# CD.net
KiCad netlist of a schematic drawn in EAGLE
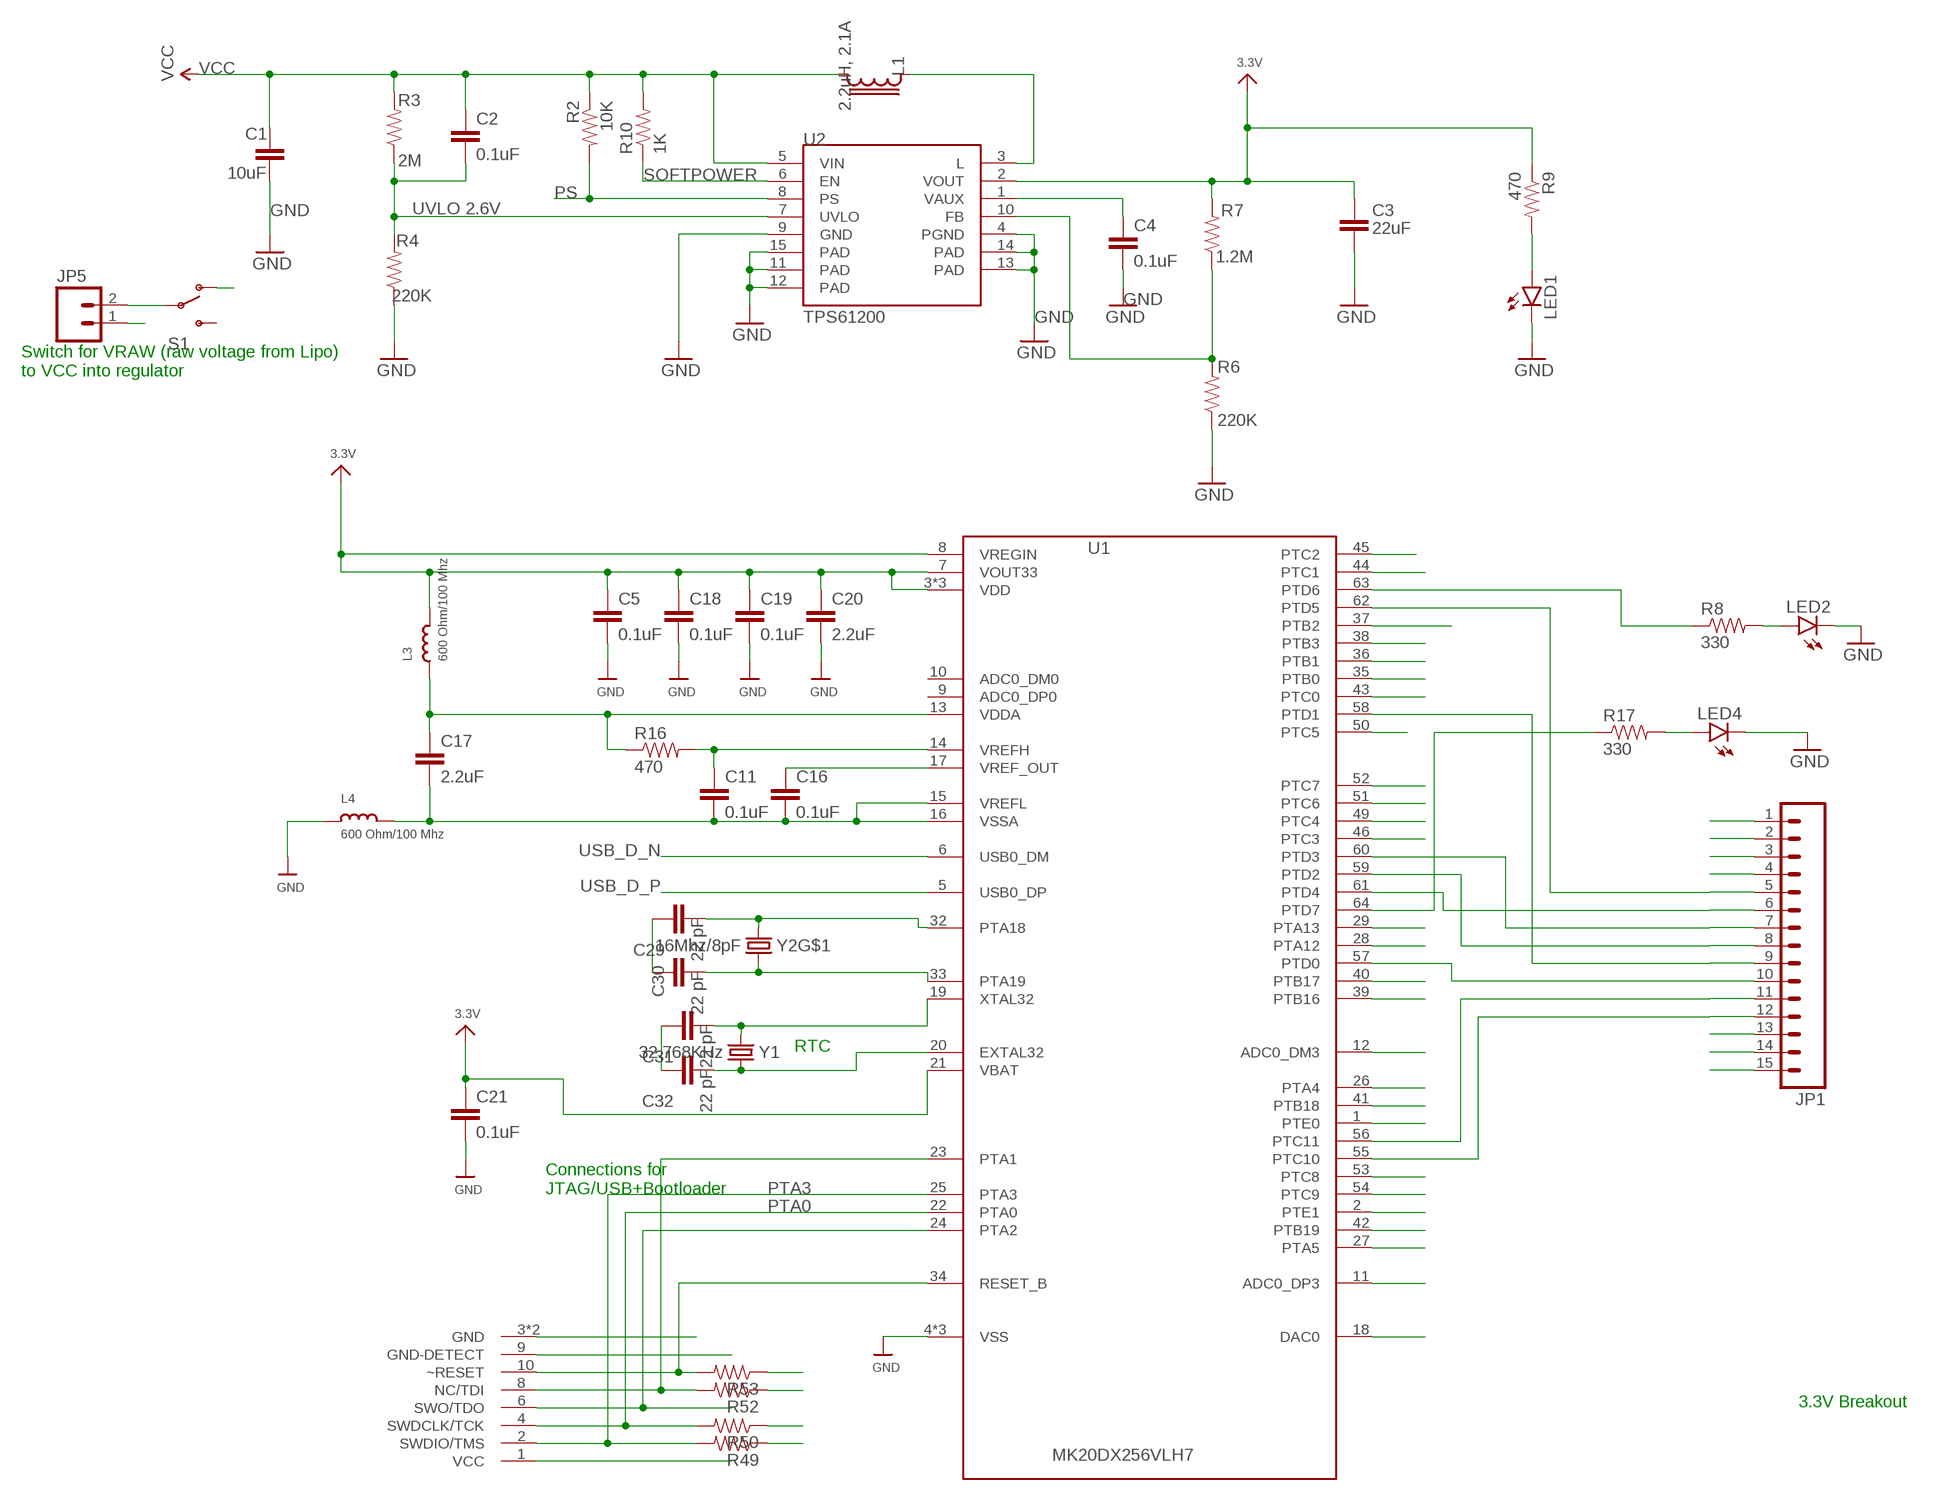
[diagram p0: schematic, sheet 1]
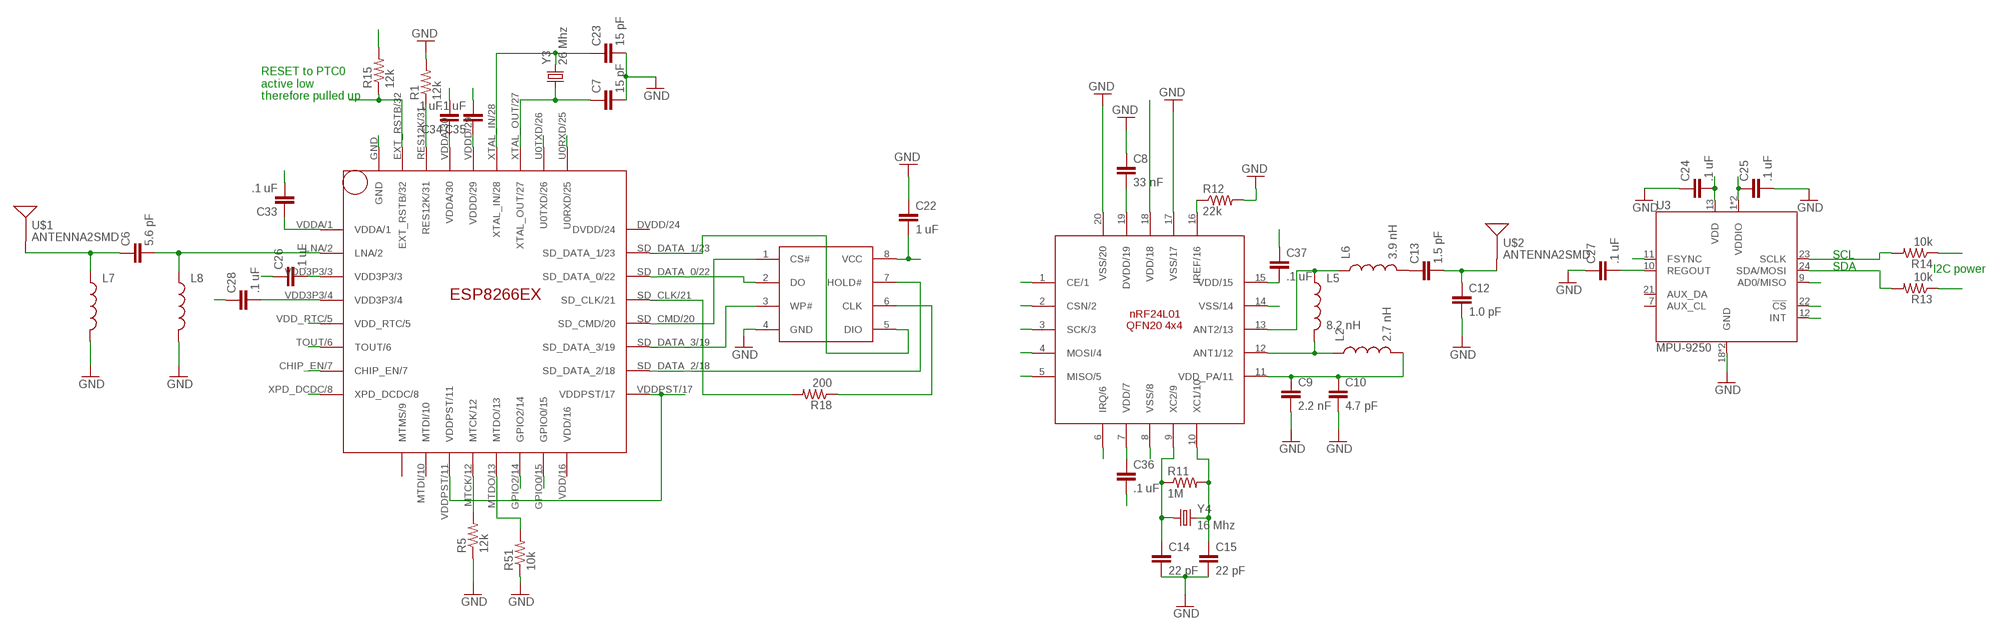
[diagram p1: schematic, sheet 2]
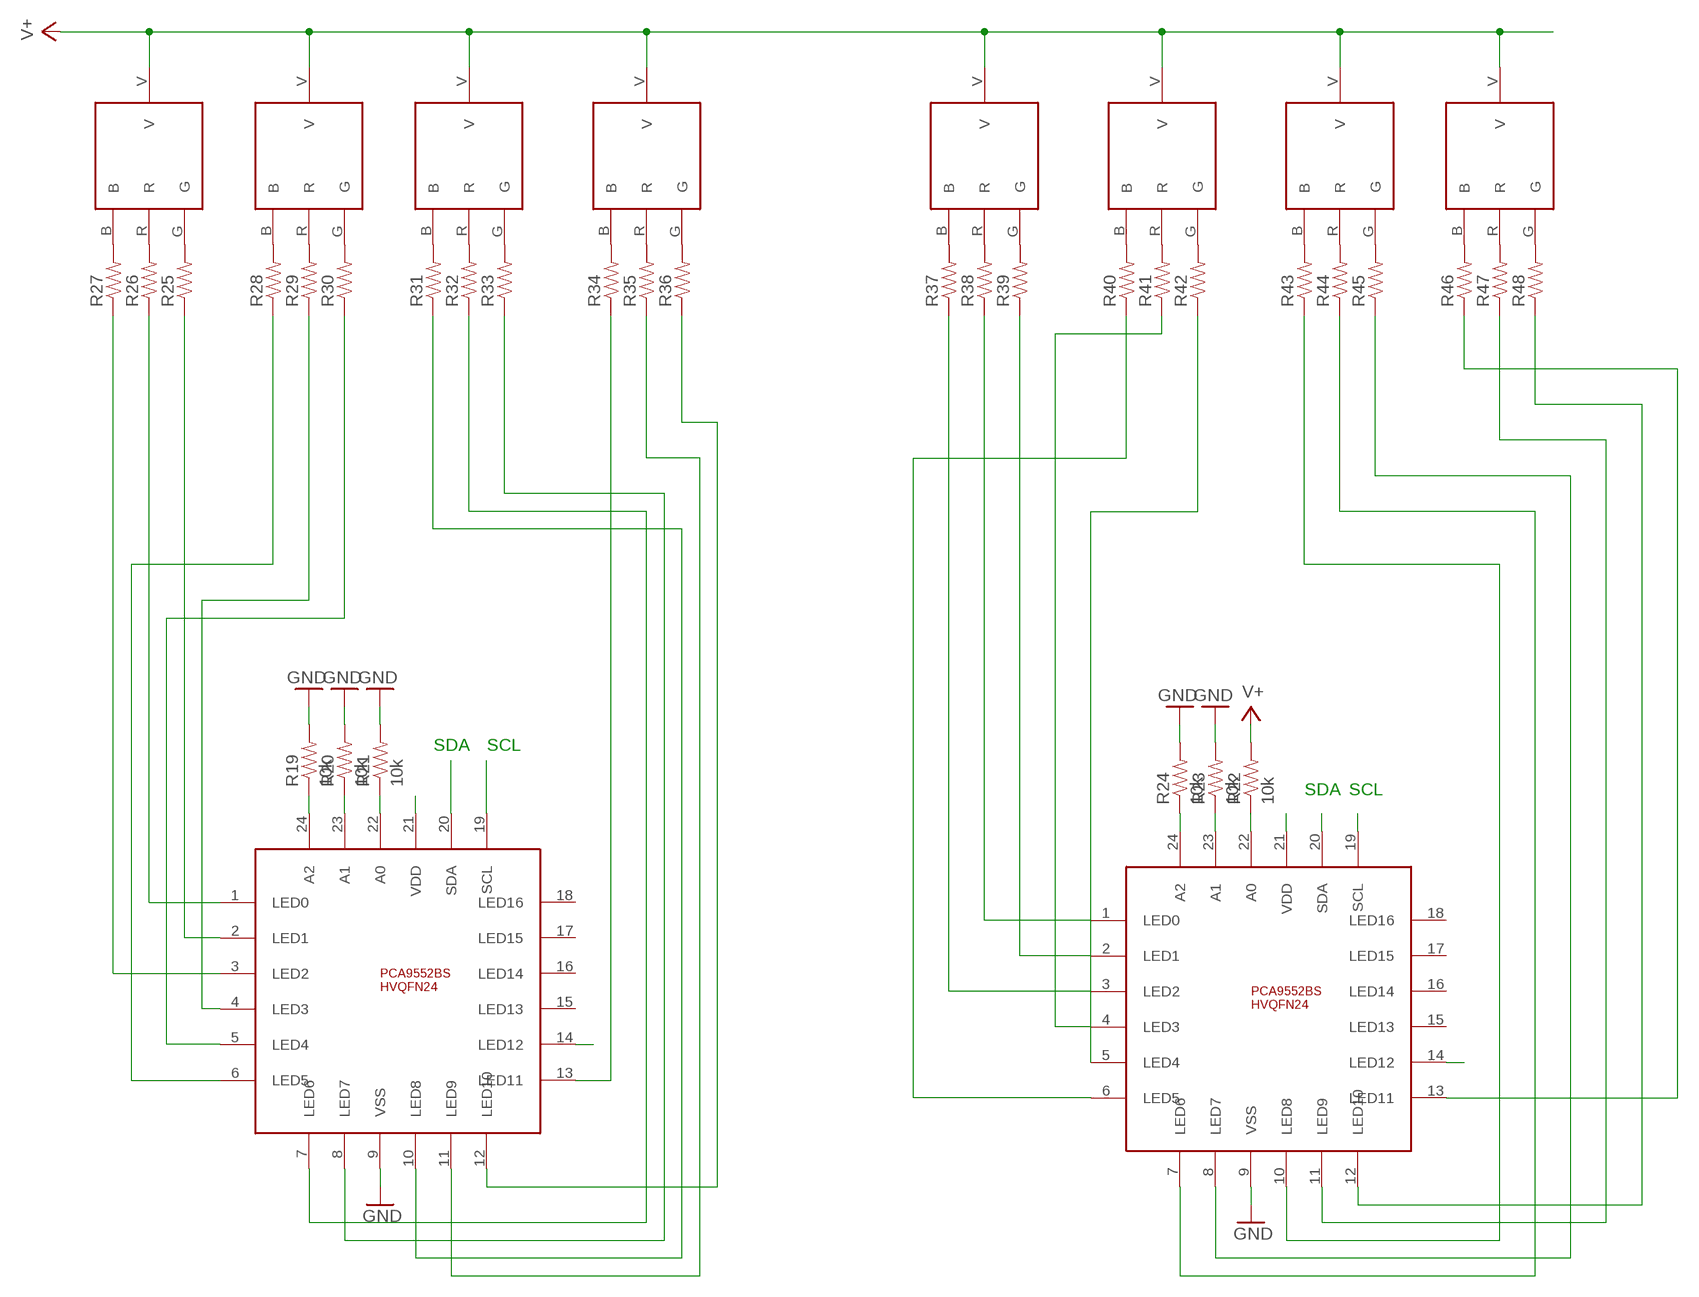
[diagram p2: schematic, sheet 3]

(export (version "E")
  (design (tool "Eeschema 10.0.6"))
  (components
    (comp (ref "C6")
      (value "5.6 pF")
      (footprint "eagle-import:0603-CAP")
      (libsource (lib "eagle-import") (part "CAP0603-CAP"))
    )
    (comp (ref "C7")
      (value "15 pF")
      (footprint "eagle-import:0603-CAP")
      (libsource (lib "eagle-import") (part "CAP0603-CAP"))
    )
    (comp (ref "C8")
      (value "33 nF")
      (footprint "eagle-import:0603-CAP")
      (libsource (lib "eagle-import") (part "CAP0603-CAP"))
    )
    (comp (ref "C9")
      (value "2.2 nF")
      (footprint "eagle-import:0603-CAP")
      (libsource (lib "eagle-import") (part "CAP0603-CAP"))
    )
    (comp (ref "C10")
      (value "4.7 pF")
      (footprint "eagle-import:0603-CAP")
      (libsource (lib "eagle-import") (part "CAP0603-CAP"))
    )
    (comp (ref "C12")
      (value "1.0 pF")
      (footprint "eagle-import:0603-CAP")
      (libsource (lib "eagle-import") (part "CAP0603-CAP"))
    )
    (comp (ref "C13")
      (value "1.5 pF")
      (footprint "eagle-import:0603-CAP")
      (libsource (lib "eagle-import") (part "CAP0603-CAP"))
    )
    (comp (ref "C14")
      (value "22 pF")
      (footprint "eagle-import:0603-CAP")
      (libsource (lib "eagle-import") (part "CAP0603-CAP"))
    )
    (comp (ref "C15")
      (value "22 pF")
      (footprint "eagle-import:0603-CAP")
      (libsource (lib "eagle-import") (part "CAP0603-CAP"))
    )
    (comp (ref "C22")
      (value "1 uF")
      (footprint "eagle-import:0603-CAP")
      (libsource (lib "eagle-import") (part "CAP0603-CAP"))
    )
    (comp (ref "C23")
      (value "15 pF")
      (footprint "eagle-import:0603-CAP")
      (libsource (lib "eagle-import") (part "CAP0603-CAP"))
    )
    (comp (ref "C24")
      (value ".1 uF")
      (footprint "eagle-import:0603-CAP")
      (libsource (lib "eagle-import") (part "CAP0603-CAP"))
    )
    (comp (ref "C25")
      (value ".1 uF")
      (footprint "eagle-import:0603-CAP")
      (libsource (lib "eagle-import") (part "CAP0603-CAP"))
    )
    (comp (ref "C26")
      (value ".1 uF")
      (footprint "eagle-import:0603-CAP")
      (libsource (lib "eagle-import") (part "CAP0603-CAP"))
    )
    (comp (ref "C27")
      (value ".1 uF")
      (footprint "eagle-import:0603-CAP")
      (libsource (lib "eagle-import") (part "CAP0603-CAP"))
    )
    (comp (ref "C28")
      (value ".1 uF")
      (footprint "eagle-import:0603-CAP")
      (libsource (lib "eagle-import") (part "CAP0603-CAP"))
    )
    (comp (ref "C33")
      (value ".1 uF")
      (footprint "eagle-import:0603-CAP")
      (libsource (lib "eagle-import") (part "CAP0603-CAP"))
    )
    (comp (ref "C34")
      (value ".1 uF")
      (footprint "eagle-import:0603-CAP")
      (libsource (lib "eagle-import") (part "CAP0603-CAP"))
    )
    (comp (ref "C35")
      (value ".1 uF")
      (footprint "eagle-import:0603-CAP")
      (libsource (lib "eagle-import") (part "CAP0603-CAP"))
    )
    (comp (ref "C36")
      (value ".1 uF")
      (footprint "eagle-import:0603-CAP")
      (libsource (lib "eagle-import") (part "CAP0603-CAP"))
    )
    (comp (ref "C37")
      (value ".1 uF")
      (footprint "eagle-import:0603-CAP")
      (libsource (lib "eagle-import") (part "CAP0603-CAP"))
    )
    (comp (ref "L2")
      (value "2.7 nH")
      (footprint "eagle-import:C0402")
      (libsource (lib "eagle-import") (part "INDUCTOR0402"))
    )
    (comp (ref "L5")
      (value "8.2 nH")
      (footprint "eagle-import:C0402")
      (libsource (lib "eagle-import") (part "INDUCTOR0402"))
    )
    (comp (ref "L6")
      (value "3.9 nH")
      (footprint "eagle-import:C0402")
      (libsource (lib "eagle-import") (part "INDUCTOR0402"))
    )
    (comp (ref "L7")
      (value "INDUCTOR30OHM,1.8A")
      (footprint "eagle-import:0603")
      (libsource (lib "eagle-import") (part "INDUCTOR30OHM,1.8A"))
    )
    (comp (ref "L8")
      (value "INDUCTOR30OHM,1.8A")
      (footprint "eagle-import:0603")
      (libsource (lib "eagle-import") (part "INDUCTOR30OHM,1.8A"))
    )
    (comp (ref "R1")
      (value "12k")
      (footprint "eagle-import:0603-RES")
      (libsource (lib "eagle-import") (part "SparkFun-Resistors_RESISTOR0603-RES"))
    )
    (comp (ref "R5")
      (value "12k")
      (footprint "eagle-import:0603-RES")
      (libsource (lib "eagle-import") (part "SparkFun-Resistors_RESISTOR0603-RES"))
    )
    (comp (ref "R11")
      (value "1M")
      (footprint "eagle-import:0603-RES")
      (libsource (lib "eagle-import") (part "SparkFun-Resistors_RESISTOR0603-RES"))
    )
    (comp (ref "R12")
      (value "22k")
      (footprint "eagle-import:0603-RES")
      (libsource (lib "eagle-import") (part "SparkFun-Resistors_RESISTOR0603-RES"))
    )
    (comp (ref "R13")
      (value "10k")
      (footprint "eagle-import:0603-RES")
      (libsource (lib "eagle-import") (part "SparkFun-Resistors_RESISTOR0603-RES"))
    )
    (comp (ref "R14")
      (value "10k")
      (footprint "eagle-import:0603-RES")
      (libsource (lib "eagle-import") (part "SparkFun-Resistors_RESISTOR0603-RES"))
    )
    (comp (ref "R15")
      (value "12k")
      (footprint "eagle-import:0603-RES")
      (libsource (lib "eagle-import") (part "SparkFun-Resistors_RESISTOR0603-RES"))
    )
    (comp (ref "R18")
      (value "200")
      (footprint "eagle-import:0603-RES")
      (libsource (lib "eagle-import") (part "SparkFun-Resistors_RESISTOR0603-RES"))
    )
    (comp (ref "R51")
      (value "10k")
      (footprint "eagle-import:0603-RES")
      (libsource (lib "eagle-import") (part "SparkFun-Resistors_RESISTOR0603-RES"))
    )
    (comp (ref "U$1")
      (value "ANTENNA2SMD")
      (footprint "eagle-import:ANTENNA-CHIP2")
      (libsource (lib "eagle-import") (part "ANTENNA2SMD"))
    )
    (comp (ref "U$2")
      (value "ANTENNA2SMD")
      (footprint "eagle-import:ANTENNA-CHIP2")
      (libsource (lib "eagle-import") (part "ANTENNA2SMD"))
    )
    (comp (ref "U$3")
      (value "25Q40")
      (footprint "eagle-import:SOP8")
      (libsource (lib "eagle-import") (part "25Q40"))
    )
    (comp (ref "U$4")
      (value "NRF24L01")
      (footprint "eagle-import:QFN20(4X4)")
      (libsource (lib "eagle-import") (part "NRF24L01"))
    )
    (comp (ref "U$6")
      (value "ESP8266EX")
      (footprint "eagle-import:QFN32")
      (libsource (lib "eagle-import") (part "ESP8266EX"))
    )
    (comp (ref "U3")
      (value "MPU-9250")
      (footprint "eagle-import:QFN-24_3MM")
      (libsource (lib "eagle-import") (part "MPU-9250"))
    )
    (comp (ref "Y3")
      (value "26 Mhz")
      (footprint "eagle-import:CRYSTAL-SMD-5X3")
      (libsource (lib "eagle-import") (part "CRYSTAL5X3"))
    )
    (comp (ref "Y4")
      (value "16 Mhz")
      (footprint "eagle-import:CRYSTAL-SMD-5X3")
      (libsource (lib "eagle-import") (part "CRYSTAL5X3"))
    )
    (comp (ref "C1")
      (value "10uF")
      (footprint "eagle-import:0603-CAP")
      (fields (field (name "MF") "Murata") (field (name "MPN") "GRM188R60J106ME47D"))
      (libsource (lib "eagle-import") (part "CAPACITOR-10UF"))
    )
    (comp (ref "C2")
      (value "0.1uF")
      (footprint "eagle-import:0603-CAP")
      (fields (field (name "MF") "Kemet") (field (name "MPN") "C0603C104J3RACTU"))
      (libsource (lib "eagle-import") (part "CAPACITOR-0.1UF"))
    )
    (comp (ref "C3")
      (value "22uF")
      (footprint "eagle-import:0603-CAP")
      (fields (field (name "MF") "Murata") (field (name "MPN") "GRM188R60J226MEA0D"))
      (libsource (lib "eagle-import") (part "CAPACITOR-22UF"))
    )
    (comp (ref "C4")
      (value "0.1uF")
      (footprint "eagle-import:0603-CAP")
      (fields (field (name "MF") "Kemet") (field (name "MPN") "C0603C104J3RACTU"))
      (libsource (lib "eagle-import") (part "CAPACITOR-0.1UF"))
    )
    (comp (ref "C5")
      (value "0.1uF")
      (footprint "eagle-import:0603-CAP")
      (fields (field (name "MF") "Kemet") (field (name "MPN") "C0603C104J3RACTU"))
      (libsource (lib "eagle-import") (part "CAPACITOR-0.1UF"))
    )
    (comp (ref "C11")
      (value "0.1uF")
      (footprint "eagle-import:0603-CAP")
      (fields (field (name "MF") "Kemet") (field (name "MPN") "C0603C104J3RACTU"))
      (libsource (lib "eagle-import") (part "CAPACITOR-0.1UF"))
    )
    (comp (ref "C16")
      (value "0.1uF")
      (footprint "eagle-import:0603-CAP")
      (fields (field (name "MF") "Kemet") (field (name "MPN") "C0603C104J3RACTU"))
      (libsource (lib "eagle-import") (part "CAPACITOR-0.1UF"))
    )
    (comp (ref "C17")
      (value "2.2uF")
      (footprint "eagle-import:0603-CAP")
      (fields (field (name "MF") "Kemet") (field (name "MPN") "C0603C225K4PACTU"))
      (libsource (lib "eagle-import") (part "CAPACITOR-2.2UF"))
    )
    (comp (ref "C18")
      (value "0.1uF")
      (footprint "eagle-import:0603-CAP")
      (fields (field (name "MF") "Kemet") (field (name "MPN") "C0603C104J3RACTU"))
      (libsource (lib "eagle-import") (part "CAPACITOR-0.1UF"))
    )
    (comp (ref "C19")
      (value "0.1uF")
      (footprint "eagle-import:0603-CAP")
      (fields (field (name "MF") "Kemet") (field (name "MPN") "C0603C104J3RACTU"))
      (libsource (lib "eagle-import") (part "CAPACITOR-0.1UF"))
    )
    (comp (ref "C20")
      (value "2.2uF")
      (footprint "eagle-import:0603-CAP")
      (fields (field (name "MF") "Kemet") (field (name "MPN") "C0603C225K4PACTU"))
      (libsource (lib "eagle-import") (part "CAPACITOR-2.2UF"))
    )
    (comp (ref "C21")
      (value "0.1uF")
      (footprint "eagle-import:0603-CAP")
      (fields (field (name "MF") "Kemet") (field (name "MPN") "C0603C104J3RACTU"))
      (libsource (lib "eagle-import") (part "CAPACITOR-0.1UF"))
    )
    (comp (ref "C29")
      (value "22 pF")
      (footprint "eagle-import:0603-CAP")
      (fields (field (name "MF") "Murata") (field (name "MPN") "GRM188R60J106ME47D"))
      (libsource (lib "eagle-import") (part "CAPACITOR-10UF"))
    )
    (comp (ref "C30")
      (value "22 pF")
      (footprint "eagle-import:0603-CAP")
      (fields (field (name "MF") "Murata") (field (name "MPN") "GRM188R60J106ME47D"))
      (libsource (lib "eagle-import") (part "CAPACITOR-10UF"))
    )
    (comp (ref "C31")
      (value "22 pF")
      (footprint "eagle-import:0603-CAP")
      (fields (field (name "MF") "Murata") (field (name "MPN") "GRM188R60J106ME47D"))
      (libsource (lib "eagle-import") (part "CAPACITOR-10UF"))
    )
    (comp (ref "C32")
      (value "22 pF")
      (footprint "eagle-import:0603-CAP")
      (fields (field (name "MF") "Murata") (field (name "MPN") "GRM188R60J106ME47D"))
      (libsource (lib "eagle-import") (part "CAPACITOR-10UF"))
    )
    (comp (ref "JP1")
      (value "M15")
      (footprint "eagle-import:1X15")
      (libsource (lib "eagle-import") (part "M15"))
    )
    (comp (ref "JP5")
      (value "M02PTH")
      (footprint "eagle-import:1X02")
      (libsource (lib "eagle-import") (part "M02PTH"))
    )
    (comp (ref "L1")
      (value "2.2uH, 2.1A")
      (footprint "eagle-import:LPS3015")
      (fields (field (name "MF") "Coilcraft") (field (name "MPN") "LPS3015-222MRB"))
      (libsource (lib "eagle-import") (part "LPS30152.2UH"))
    )
    (comp (ref "L3")
      (value "600 Ohm/100 Mhz")
      (footprint "eagle-import:0805")
      (fields (field (name "MF") "Taiyo Yuden") (field (name "MPN") "BK2125HM601-T"))
      (libsource (lib "eagle-import") (part "INDUCTOR-BK2125HM601-T"))
    )
    (comp (ref "L4")
      (value "600 Ohm/100 Mhz")
      (footprint "eagle-import:0805")
      (fields (field (name "MF") "Taiyo Yuden") (field (name "MPN") "BK2125HM601-T"))
      (libsource (lib "eagle-import") (part "INDUCTOR-BK2125HM601-T"))
    )
    (comp (ref "LED1")
      (value "LED-GREEN")
      (footprint "eagle-import:LED-0603")
      (fields (field (name "MF") "Avago") (field (name "MPN") "HSMG-C190"))
      (libsource (lib "eagle-import") (part "LED-GREEN"))
    )
    (comp (ref "LED2")
      (value "LED-GREEN")
      (footprint "eagle-import:LED-0603")
      (fields (field (name "MF") "Avago") (field (name "MPN") "HSMG-C190"))
      (libsource (lib "eagle-import") (part "LED-GREEN"))
    )
    (comp (ref "LED4")
      (value "LED-GREEN")
      (footprint "eagle-import:LED-0603")
      (fields (field (name "MF") "Avago") (field (name "MPN") "HSMG-C190"))
      (libsource (lib "eagle-import") (part "LED-GREEN"))
    )
    (comp (ref "R2")
      (value "10K")
      (footprint "eagle-import:0603-RES")
      (fields (field (name "MF") "Panasonic") (field (name "MPN") "ERJ-3GEYJ103V"))
      (libsource (lib "eagle-import") (part "RESISTOR-10K"))
    )
    (comp (ref "R3")
      (value "2M")
      (footprint "eagle-import:0603-RES")
      (fields (field (name "MF") "Panasonic") (field (name "MPN") "ERJ-3GEYJ205V"))
      (libsource (lib "eagle-import") (part "RESISTOR-2M"))
    )
    (comp (ref "R4")
      (value "220K")
      (footprint "eagle-import:0603-RES")
      (fields (field (name "MF") "Panasonic") (field (name "MPN") "ERJ-3GEYJ224V"))
      (libsource (lib "eagle-import") (part "RESISTOR-220K"))
    )
    (comp (ref "R6")
      (value "220K")
      (footprint "eagle-import:0603-RES")
      (fields (field (name "MF") "Panasonic") (field (name "MPN") "ERJ-3GEYJ224V"))
      (libsource (lib "eagle-import") (part "RESISTOR-220K"))
    )
    (comp (ref "R7")
      (value "1.2M")
      (footprint "eagle-import:0603-RES")
      (fields (field (name "MF") "Panasonic") (field (name "MPN") "ERJ-3GEYJ125V"))
      (libsource (lib "eagle-import") (part "RESISTOR-1.2M"))
    )
    (comp (ref "R8")
      (value "330")
      (footprint "eagle-import:0603-RES")
      (fields (field (name "MF") "Panasonic") (field (name "MPN") "ERJ-3GEYJ471V"))
      (libsource (lib "eagle-import") (part "RESISTOR-470"))
    )
    (comp (ref "R9")
      (value "470")
      (footprint "eagle-import:0603-RES")
      (fields (field (name "MF") "Panasonic") (field (name "MPN") "ERJ-3GEYJ471V"))
      (libsource (lib "eagle-import") (part "RESISTOR-470"))
    )
    (comp (ref "R10")
      (value "1K")
      (footprint "eagle-import:0603-RES")
      (fields (field (name "MF") "Panasonic") (field (name "MPN") "ERJ-3GEYJ102V"))
      (libsource (lib "eagle-import") (part "RESISTOR-1K"))
    )
    (comp (ref "R16")
      (value "470")
      (footprint "eagle-import:0603-RES")
      (fields (field (name "MF") "Panasonic") (field (name "MPN") "ERJ-3GEYJ471V"))
      (libsource (lib "eagle-import") (part "RESISTOR-470"))
    )
    (comp (ref "R17")
      (value "330")
      (footprint "eagle-import:0603-RES")
      (fields (field (name "MF") "Panasonic") (field (name "MPN") "ERJ-3GEYJ471V"))
      (libsource (lib "eagle-import") (part "RESISTOR-470"))
    )
    (comp (ref "R49")
      (value "RESISTOR0402-RES")
      (footprint "eagle-import:0402-RES")
      (libsource (lib "eagle-import") (part "RESISTOR0402-RES"))
    )
    (comp (ref "R50")
      (value "RESISTOR0402-RES")
      (footprint "eagle-import:0402-RES")
      (libsource (lib "eagle-import") (part "RESISTOR0402-RES"))
    )
    (comp (ref "R52")
      (value "RESISTOR0402-RES")
      (footprint "eagle-import:0402-RES")
      (libsource (lib "eagle-import") (part "RESISTOR0402-RES"))
    )
    (comp (ref "R53")
      (value "RESISTOR0402-RES")
      (footprint "eagle-import:0402-RES")
      (libsource (lib "eagle-import") (part "RESISTOR0402-RES"))
    )
    (comp (ref "S1")
      (value "SWITCH-SPDT-SMD-A")
      (footprint "eagle-import:SWITCH-SPST-SMD-A")
      (libsource (lib "eagle-import") (part "SWITCH-SPDT-SMD-A"))
    )
    (comp (ref "U$7")
      (value "2X5_0.05\"_CORTEX_DEBUGTH_NOKEY_UNSHROUDED")
      (footprint "eagle-import:2X5_0.05__TH_NS")
      (libsource (lib "eagle-import") (part "2X5_0.05{dblquote}_CORTEX_DEBUGTH_NOKEY_UNSHROUDED"))
    )
    (comp (ref "U1")
      (value "MK20DX256VLH7")
      (footprint "eagle-import:MK20DX256VLH7")
      (fields (field (name "MF") "Freescale"))
      (libsource (lib "eagle-import") (part "MK20DX256VLH7"))
    )
    (comp (ref "U2")
      (value "TPS61200")
      (footprint "eagle-import:QFN-10_PAD")
      (fields (field (name "MF") "Texas Instruments") (field (name "MPN") "TPS61200DRCR"))
      (libsource (lib "eagle-import") (part "TPS61200"))
    )
    (comp (ref "Y1")
      (value "32.768KHz")
      (footprint "eagle-import:CRYSTAL-TXC-7A")
      (fields (field (name "MF") "Epson Timing") (field (name "MPN") "FC-255 32.7680K-A3"))
      (libsource (lib "eagle-import") (part "CRYSTAL/32.768KHZ/SMD-TXC_7A"))
    )
    (comp (ref "Y2")
      (value "16Mhz/8pF")
      (footprint "eagle-import:CRYSTAL-SMD-5X3")
      (fields (field (name "MF") "ECS") (field (name "MPN") "ECS-160-8-30B-CKM"))
      (libsource (lib "eagle-import") (part "CRYSTAL/SMD-5X3-GND16MHZ/8PF"))
    )
    (comp (ref "R19")
      (value "10k")
      (footprint "eagle-import:0603-RES")
      (libsource (lib "eagle-import") (part "RESISTOR0603-RES"))
    )
    (comp (ref "R20")
      (value "10k")
      (footprint "eagle-import:0603-RES")
      (libsource (lib "eagle-import") (part "RESISTOR0603-RES"))
    )
    (comp (ref "R21")
      (value "10k")
      (footprint "eagle-import:0603-RES")
      (libsource (lib "eagle-import") (part "RESISTOR0603-RES"))
    )
    (comp (ref "R22")
      (value "10k")
      (footprint "eagle-import:0603-RES")
      (libsource (lib "eagle-import") (part "RESISTOR0603-RES"))
    )
    (comp (ref "R23")
      (value "10k")
      (footprint "eagle-import:0603-RES")
      (libsource (lib "eagle-import") (part "RESISTOR0603-RES"))
    )
    (comp (ref "R24")
      (value "10k")
      (footprint "eagle-import:0603-RES")
      (libsource (lib "eagle-import") (part "RESISTOR0603-RES"))
    )
    (comp (ref "R25")
      (value "RESISTOR0402-RES")
      (footprint "eagle-import:0402-RES")
      (libsource (lib "eagle-import") (part "RESISTOR0402-RES"))
    )
    (comp (ref "R26")
      (value "RESISTOR0402-RES")
      (footprint "eagle-import:0402-RES")
      (libsource (lib "eagle-import") (part "RESISTOR0402-RES"))
    )
    (comp (ref "R27")
      (value "RESISTOR0402-RES")
      (footprint "eagle-import:0402-RES")
      (libsource (lib "eagle-import") (part "RESISTOR0402-RES"))
    )
    (comp (ref "R28")
      (value "RESISTOR0402-RES")
      (footprint "eagle-import:0402-RES")
      (libsource (lib "eagle-import") (part "RESISTOR0402-RES"))
    )
    (comp (ref "R29")
      (value "RESISTOR0402-RES")
      (footprint "eagle-import:0402-RES")
      (libsource (lib "eagle-import") (part "RESISTOR0402-RES"))
    )
    (comp (ref "R30")
      (value "RESISTOR0402-RES")
      (footprint "eagle-import:0402-RES")
      (libsource (lib "eagle-import") (part "RESISTOR0402-RES"))
    )
    (comp (ref "R31")
      (value "RESISTOR0402-RES")
      (footprint "eagle-import:0402-RES")
      (libsource (lib "eagle-import") (part "RESISTOR0402-RES"))
    )
    (comp (ref "R32")
      (value "RESISTOR0402-RES")
      (footprint "eagle-import:0402-RES")
      (libsource (lib "eagle-import") (part "RESISTOR0402-RES"))
    )
    (comp (ref "R33")
      (value "RESISTOR0402-RES")
      (footprint "eagle-import:0402-RES")
      (libsource (lib "eagle-import") (part "RESISTOR0402-RES"))
    )
    (comp (ref "R34")
      (value "RESISTOR0402-RES")
      (footprint "eagle-import:0402-RES")
      (libsource (lib "eagle-import") (part "RESISTOR0402-RES"))
    )
    (comp (ref "R35")
      (value "RESISTOR0402-RES")
      (footprint "eagle-import:0402-RES")
      (libsource (lib "eagle-import") (part "RESISTOR0402-RES"))
    )
    (comp (ref "R36")
      (value "RESISTOR0402-RES")
      (footprint "eagle-import:0402-RES")
      (libsource (lib "eagle-import") (part "RESISTOR0402-RES"))
    )
    (comp (ref "R37")
      (value "RESISTOR0402-RES")
      (footprint "eagle-import:0402-RES")
      (libsource (lib "eagle-import") (part "RESISTOR0402-RES"))
    )
    (comp (ref "R38")
      (value "RESISTOR0402-RES")
      (footprint "eagle-import:0402-RES")
      (libsource (lib "eagle-import") (part "RESISTOR0402-RES"))
    )
    (comp (ref "R39")
      (value "RESISTOR0402-RES")
      (footprint "eagle-import:0402-RES")
      (libsource (lib "eagle-import") (part "RESISTOR0402-RES"))
    )
    (comp (ref "R40")
      (value "RESISTOR0402-RES")
      (footprint "eagle-import:0402-RES")
      (libsource (lib "eagle-import") (part "RESISTOR0402-RES"))
    )
    (comp (ref "R41")
      (value "RESISTOR0402-RES")
      (footprint "eagle-import:0402-RES")
      (libsource (lib "eagle-import") (part "RESISTOR0402-RES"))
    )
    (comp (ref "R42")
      (value "RESISTOR0402-RES")
      (footprint "eagle-import:0402-RES")
      (libsource (lib "eagle-import") (part "RESISTOR0402-RES"))
    )
    (comp (ref "R43")
      (value "RESISTOR0402-RES")
      (footprint "eagle-import:0402-RES")
      (libsource (lib "eagle-import") (part "RESISTOR0402-RES"))
    )
    (comp (ref "R44")
      (value "RESISTOR0402-RES")
      (footprint "eagle-import:0402-RES")
      (libsource (lib "eagle-import") (part "RESISTOR0402-RES"))
    )
    (comp (ref "R45")
      (value "RESISTOR0402-RES")
      (footprint "eagle-import:0402-RES")
      (libsource (lib "eagle-import") (part "RESISTOR0402-RES"))
    )
    (comp (ref "R46")
      (value "RESISTOR0402-RES")
      (footprint "eagle-import:0402-RES")
      (libsource (lib "eagle-import") (part "RESISTOR0402-RES"))
    )
    (comp (ref "R47")
      (value "RESISTOR0402-RES")
      (footprint "eagle-import:0402-RES")
      (libsource (lib "eagle-import") (part "RESISTOR0402-RES"))
    )
    (comp (ref "R48")
      (value "RESISTOR0402-RES")
      (footprint "eagle-import:0402-RES")
      (libsource (lib "eagle-import") (part "RESISTOR0402-RES"))
    )
    (comp (ref "U$8")
      (value "LTST-C19FD1WT")
      (footprint "eagle-import:LTST-C19FD1WT")
      (libsource (lib "eagle-import") (part "LTST-C19FD1WT"))
    )
    (comp (ref "U$11")
      (value "LTST-C19FD1WT")
      (footprint "eagle-import:LTST-C19FD1WT")
      (libsource (lib "eagle-import") (part "LTST-C19FD1WT"))
    )
    (comp (ref "U$13")
      (value "LTST-C19FD1WT")
      (footprint "eagle-import:LTST-C19FD1WT")
      (libsource (lib "eagle-import") (part "LTST-C19FD1WT"))
    )
    (comp (ref "U$14")
      (value "LTST-C19FD1WT")
      (footprint "eagle-import:LTST-C19FD1WT")
      (libsource (lib "eagle-import") (part "LTST-C19FD1WT"))
    )
    (comp (ref "U$15")
      (value "LTST-C19FD1WT")
      (footprint "eagle-import:LTST-C19FD1WT")
      (libsource (lib "eagle-import") (part "LTST-C19FD1WT"))
    )
    (comp (ref "U$16")
      (value "LTST-C19FD1WT")
      (footprint "eagle-import:LTST-C19FD1WT")
      (libsource (lib "eagle-import") (part "LTST-C19FD1WT"))
    )
    (comp (ref "U$17")
      (value "LTST-C19FD1WT")
      (footprint "eagle-import:LTST-C19FD1WT")
      (libsource (lib "eagle-import") (part "LTST-C19FD1WT"))
    )
    (comp (ref "U$18")
      (value "LTST-C19FD1WT")
      (footprint "eagle-import:LTST-C19FD1WT")
      (libsource (lib "eagle-import") (part "LTST-C19FD1WT"))
    )
    (comp (ref "U$20")
      (value "PCA9552BS")
      (footprint "eagle-import:HVQFN24")
      (libsource (lib "eagle-import") (part "PCA9552BS"))
    )
    (comp (ref "U$21")
      (value "PCA9552BS")
      (footprint "eagle-import:HVQFN24")
      (libsource (lib "eagle-import") (part "PCA9552BS"))
    )
  )
  (nets
    (net (code "1") (name "3.3V") (class "Default")
      (node (ref "C18") (pin "1") (pinfunction "1_1") (pintype "passive"))
      (node (ref "C19") (pin "1") (pinfunction "1_1") (pintype "passive"))
      (node (ref "C20") (pin "1") (pinfunction "1_1") (pintype "passive"))
      (node (ref "C21") (pin "1") (pinfunction "1_1") (pintype "passive"))
      (node (ref "C22") (pin "2") (pinfunction "2_2") (pintype "passive"))
      (node (ref "C24") (pin "2") (pinfunction "2_2") (pintype "passive"))
      (node (ref "C25") (pin "1") (pinfunction "1_1") (pintype "passive"))
      (node (ref "C26") (pin "2") (pinfunction "2_2") (pintype "passive"))
      (node (ref "C28") (pin "2") (pinfunction "2_2") (pintype "passive"))
      (node (ref "C3") (pin "1") (pinfunction "1_1") (pintype "passive"))
      (node (ref "C33") (pin "1") (pinfunction "1_1") (pintype "passive"))
      (node (ref "C34") (pin "1") (pinfunction "1_1") (pintype "passive"))
      (node (ref "C35") (pin "1") (pinfunction "1_1") (pintype "passive"))
      (node (ref "C36") (pin "1") (pinfunction "1_1") (pintype "passive"))
      (node (ref "C37") (pin "2") (pinfunction "2_2") (pintype "passive"))
      (node (ref "C5") (pin "1") (pinfunction "1_1") (pintype "passive"))
      (node (ref "JP1") (pin "13") (pinfunction "13_13") (pintype "passive"))
      (node (ref "JP1") (pin "14") (pinfunction "14_14") (pintype "passive"))
      (node (ref "JP1") (pin "15") (pinfunction "15_15") (pintype "passive"))
      (node (ref "L3") (pin "2") (pinfunction "2_2") (pintype "passive"))
      (node (ref "R13") (pin "1") (pinfunction "1_1") (pintype "passive"))
      (node (ref "R14") (pin "1") (pinfunction "1_1") (pintype "passive"))
      (node (ref "R15") (pin "2") (pinfunction "2_2") (pintype "passive"))
      (node (ref "R22") (pin "2") (pinfunction "2_2") (pintype "passive"))
      (node (ref "R49") (pin "1") (pinfunction "1_1") (pintype "passive"))
      (node (ref "R52") (pin "1") (pinfunction "1_1") (pintype "passive"))
      (node (ref "R53") (pin "1") (pinfunction "1_1") (pintype "passive"))
      (node (ref "R7") (pin "2") (pinfunction "2_2") (pintype "passive"))
      (node (ref "R9") (pin "1") (pinfunction "1_1") (pintype "passive"))
      (node (ref "U$11") (pin "V") (pinfunction "V_V") (pintype "bidirectional"))
      (node (ref "U$13") (pin "V") (pinfunction "V_V") (pintype "bidirectional"))
      (node (ref "U$14") (pin "V") (pinfunction "V_V") (pintype "bidirectional"))
      (node (ref "U$15") (pin "V") (pinfunction "V_V") (pintype "bidirectional"))
      (node (ref "U$16") (pin "V") (pinfunction "V_V") (pintype "bidirectional"))
      (node (ref "U$17") (pin "V") (pinfunction "V_V") (pintype "bidirectional"))
      (node (ref "U$18") (pin "V") (pinfunction "V_V") (pintype "bidirectional"))
      (node (ref "U$20") (pin "21") (pinfunction "VDD_21") (pintype "bidirectional"))
      (node (ref "U$21") (pin "21") (pinfunction "VDD_21") (pintype "bidirectional"))
      (node (ref "U$3") (pin "8") (pinfunction "VCC_8") (pintype "bidirectional"))
      (node (ref "U$4") (pin "15") (pinfunction "VDD/15_15") (pintype "bidirectional"))
      (node (ref "U$4") (pin "18") (pinfunction "VDD/18_18") (pintype "bidirectional"))
      (node (ref "U$4") (pin "7") (pinfunction "VDD/7_7") (pintype "bidirectional"))
      (node (ref "U$6") (pin "VDD3P3/3") (pinfunction "VDD3P3/3_VDD3P3/3") (pintype "bidirectional"))
      (node (ref "U$6") (pin "VDD3P3/4") (pinfunction "VDD3P3/4_VDD3P3/4") (pintype "bidirectional"))
      (node (ref "U$6") (pin "VDDA/1") (pinfunction "VDDA/1_VDDA/1") (pintype "bidirectional"))
      (node (ref "U$6") (pin "VDDA/30") (pinfunction "VDDA/30_VDDA/30") (pintype "bidirectional"))
      (node (ref "U$6") (pin "VDDD/29") (pinfunction "VDDD/29_VDDD/29") (pintype "bidirectional"))
      (node (ref "U$6") (pin "VDDPST/11") (pinfunction "VDDPST/11_VDDPST/11") (pintype "bidirectional"))
      (node (ref "U$6") (pin "VDDPST/17") (pinfunction "VDDPST/17_VDDPST/17") (pintype "bidirectional"))
      (node (ref "U$7") (pin "1") (pinfunction "VCC_1") (pintype "bidirectional"))
      (node (ref "U$8") (pin "V") (pinfunction "V_V") (pintype "bidirectional"))
      (node (ref "U1") (pin "21") (pinfunction "VBAT_21") (pintype "bidirectional"))
      (node (ref "U1") (pin "3") (pinfunction "VDD_3") (pintype "bidirectional"))
      (node (ref "U1") (pin "30") (pinfunction "VDD_30") (pintype "bidirectional"))
      (node (ref "U1") (pin "48") (pinfunction "VDD_48") (pintype "bidirectional"))
      (node (ref "U1") (pin "7") (pinfunction "VOUT33_7") (pintype "bidirectional"))
      (node (ref "U1") (pin "8") (pinfunction "VREGIN_8") (pintype "bidirectional"))
      (node (ref "U2") (pin "2") (pinfunction "VOUT_2") (pintype "passive"))
      (node (ref "U3") (pin "1") (pinfunction "VDDIO_1") (pintype "bidirectional"))
      (node (ref "U3") (pin "13") (pinfunction "VDD_13") (pintype "bidirectional"))
      (node (ref "U3") (pin "22") (pinfunction "~{CS}_22") (pintype "bidirectional"))
      (node (ref "U3") (pin "8") (pinfunction "VDDIO_8") (pintype "bidirectional"))
    )
    (net (code "2") (name "AD0") (class "Default")
      (node (ref "U1") (pin "45") (pinfunction "PTC2_45") (pintype "bidirectional"))
      (node (ref "U3") (pin "9") (pinfunction "AD0/MISO_9") (pintype "bidirectional"))
    )
    (net (code "3") (name "GND") (class "Default")
      (node (ref "C1") (pin "2") (pinfunction "2_2") (pintype "passive"))
      (node (ref "C10") (pin "2") (pinfunction "2_2") (pintype "passive"))
      (node (ref "C12") (pin "2") (pinfunction "2_2") (pintype "passive"))
      (node (ref "C14") (pin "2") (pinfunction "2_2") (pintype "passive"))
      (node (ref "C15") (pin "2") (pinfunction "2_2") (pintype "passive"))
      (node (ref "C18") (pin "2") (pinfunction "2_2") (pintype "passive"))
      (node (ref "C19") (pin "2") (pinfunction "2_2") (pintype "passive"))
      (node (ref "C20") (pin "2") (pinfunction "2_2") (pintype "passive"))
      (node (ref "C21") (pin "2") (pinfunction "2_2") (pintype "passive"))
      (node (ref "C22") (pin "1") (pinfunction "1_1") (pintype "passive"))
      (node (ref "C23") (pin "2") (pinfunction "2_2") (pintype "passive"))
      (node (ref "C24") (pin "1") (pinfunction "1_1") (pintype "passive"))
      (node (ref "C25") (pin "2") (pinfunction "2_2") (pintype "passive"))
      (node (ref "C26") (pin "1") (pinfunction "1_1") (pintype "passive"))
      (node (ref "C27") (pin "1") (pinfunction "1_1") (pintype "passive"))
      (node (ref "C28") (pin "1") (pinfunction "1_1") (pintype "passive"))
      (node (ref "C29") (pin "1") (pinfunction "1_1") (pintype "passive"))
      (node (ref "C3") (pin "2") (pinfunction "2_2") (pintype "passive"))
      (node (ref "C30") (pin "1") (pinfunction "1_1") (pintype "passive"))
      (node (ref "C31") (pin "1") (pinfunction "1_1") (pintype "passive"))
      (node (ref "C32") (pin "1") (pinfunction "1_1") (pintype "passive"))
      (node (ref "C33") (pin "2") (pinfunction "2_2") (pintype "passive"))
      (node (ref "C34") (pin "2") (pinfunction "2_2") (pintype "passive"))
      (node (ref "C35") (pin "2") (pinfunction "2_2") (pintype "passive"))
      (node (ref "C36") (pin "2") (pinfunction "2_2") (pintype "passive"))
      (node (ref "C37") (pin "1") (pinfunction "1_1") (pintype "passive"))
      (node (ref "C4") (pin "2") (pinfunction "2_2") (pintype "passive"))
      (node (ref "C5") (pin "2") (pinfunction "2_2") (pintype "passive"))
      (node (ref "C7") (pin "2") (pinfunction "2_2") (pintype "passive"))
      (node (ref "C8") (pin "1") (pinfunction "1_1") (pintype "passive"))
      (node (ref "C9") (pin "2") (pinfunction "2_2") (pintype "passive"))
      (node (ref "JP1") (pin "1") (pinfunction "1_1") (pintype "passive"))
      (node (ref "JP1") (pin "2") (pinfunction "2_2") (pintype "passive"))
      (node (ref "JP1") (pin "3") (pinfunction "3_3") (pintype "passive"))
      (node (ref "JP1") (pin "4") (pinfunction "4_4") (pintype "passive"))
      (node (ref "JP5") (pin "1") (pinfunction "1_1") (pintype "passive"))
      (node (ref "L4") (pin "1") (pinfunction "1_1") (pintype "passive"))
      (node (ref "L7") (pin "2") (pinfunction "2_2") (pintype "passive"))
      (node (ref "L8") (pin "2") (pinfunction "2_2") (pintype "passive"))
      (node (ref "LED1") (pin "C") (pinfunction "C_C") (pintype "passive"))
      (node (ref "LED2") (pin "C") (pinfunction "C_C") (pintype "passive"))
      (node (ref "LED4") (pin "C") (pinfunction "C_C") (pintype "passive"))
      (node (ref "R1") (pin "2") (pinfunction "2_2") (pintype "passive"))
      (node (ref "R12") (pin "2") (pinfunction "2_2") (pintype "passive"))
      (node (ref "R19") (pin "2") (pinfunction "2_2") (pintype "passive"))
      (node (ref "R20") (pin "2") (pinfunction "2_2") (pintype "passive"))
      (node (ref "R21") (pin "2") (pinfunction "2_2") (pintype "passive"))
      (node (ref "R23") (pin "2") (pinfunction "2_2") (pintype "passive"))
      (node (ref "R24") (pin "2") (pinfunction "2_2") (pintype "passive"))
      (node (ref "R4") (pin "1") (pinfunction "1_1") (pintype "passive"))
      (node (ref "R5") (pin "1") (pinfunction "1_1") (pintype "passive"))
      (node (ref "R50") (pin "1") (pinfunction "1_1") (pintype "passive"))
      (node (ref "R51") (pin "1") (pinfunction "1_1") (pintype "passive"))
      (node (ref "R6") (pin "1") (pinfunction "1_1") (pintype "passive"))
      (node (ref "U$20") (pin "9") (pinfunction "VSS_9") (pintype "bidirectional"))
      (node (ref "U$21") (pin "9") (pinfunction "VSS_9") (pintype "bidirectional"))
      (node (ref "U$3") (pin "4") (pinfunction "GND_4") (pintype "bidirectional"))
      (node (ref "U$4") (pin "14") (pinfunction "VSS/14_14") (pintype "bidirectional"))
      (node (ref "U$4") (pin "17") (pinfunction "VSS/17_17") (pintype "bidirectional"))
      (node (ref "U$4") (pin "20") (pinfunction "VSS/20_20") (pintype "bidirectional"))
      (node (ref "U$4") (pin "8") (pinfunction "VSS/8_8") (pintype "bidirectional"))
      (node (ref "U$6") (pin "GND") (pinfunction "GND_GND") (pintype "bidirectional"))
      (node (ref "U$7") (pin "3") (pinfunction "GND_3") (pintype "bidirectional"))
      (node (ref "U$7") (pin "5") (pinfunction "GND_5") (pintype "bidirectional"))
      (node (ref "U$7") (pin "9") (pinfunction "GND-DETECT_9") (pintype "bidirectional"))
      (node (ref "U1") (pin "31") (pinfunction "VSS_31") (pintype "bidirectional"))
      (node (ref "U1") (pin "4") (pinfunction "VSS_4") (pintype "bidirectional"))
      (node (ref "U1") (pin "47") (pinfunction "VSS_47") (pintype "bidirectional"))
      (node (ref "U2") (pin "11") (pinfunction "PAD_11") (pintype "power_in"))
      (node (ref "U2") (pin "12") (pinfunction "PAD_12") (pintype "power_in"))
      (node (ref "U2") (pin "13") (pinfunction "PAD_13") (pintype "power_in"))
      (node (ref "U2") (pin "14") (pinfunction "PAD_14") (pintype "power_in"))
      (node (ref "U2") (pin "15") (pinfunction "PAD_15") (pintype "power_in"))
      (node (ref "U2") (pin "4") (pinfunction "PGND_4") (pintype "power_in"))
      (node (ref "U2") (pin "9") (pinfunction "GND_9") (pintype "power_in"))
      (node (ref "U3") (pin "18") (pinfunction "GND_18") (pintype "bidirectional"))
      (node (ref "U3") (pin "20") (pinfunction "GND_20") (pintype "bidirectional"))
    )
    (net (code "4") (name "Net-(C6-Pad2)") (class "Default")
      (node (ref "C6") (pin "2") (pinfunction "2_2") (pintype "passive"))
      (node (ref "L8") (pin "1") (pinfunction "1_1") (pintype "passive"))
      (node (ref "U$6") (pin "LNA/2") (pinfunction "LNA/2_LNA/2") (pintype "bidirectional"))
    )
    (net (code "5") (name "Net-(C7-Pad1)") (class "Default")
      (node (ref "C7") (pin "1") (pinfunction "1_1") (pintype "passive"))
      (node (ref "U$6") (pin "XTAL_OUT/27") (pinfunction "XTAL_OUT/27_XTAL_OUT/27") (pintype "bidirectional"))
      (node (ref "Y3") (pin "1") (pinfunction "1_1") (pintype "passive"))
    )
    (net (code "6") (name "Net-(C13-Pad1)") (class "Default")
      (node (ref "C13") (pin "1") (pinfunction "1_1") (pintype "passive"))
      (node (ref "L6") (pin "2") (pinfunction "2_2") (pintype "passive"))
    )
    (net (code "7") (name "Net-(LED1-PadA)") (class "Default")
      (node (ref "LED1") (pin "A") (pinfunction "A_A") (pintype "passive"))
      (node (ref "R9") (pin "2") (pinfunction "2_2") (pintype "passive"))
    )
    (net (code "8") (name "Net-(LED2-PadA)") (class "Default")
      (node (ref "LED2") (pin "A") (pinfunction "A_A") (pintype "passive"))
      (node (ref "R8") (pin "2") (pinfunction "2_2") (pintype "passive"))
    )
    (net (code "9") (name "Net-(LED4-PadA)") (class "Default")
      (node (ref "LED4") (pin "A") (pinfunction "A_A") (pintype "passive"))
      (node (ref "R17") (pin "2") (pinfunction "2_2") (pintype "passive"))
    )
    (net (code "10") (name "Net-(R1-Pad1)") (class "Default")
      (node (ref "R1") (pin "1") (pinfunction "1_1") (pintype "passive"))
      (node (ref "U$6") (pin "RES12K/31") (pinfunction "RES12K/31_RES12K/31") (pintype "bidirectional"))
    )
    (net (code "11") (name "Net-(R5-Pad2)") (class "Default")
      (node (ref "R5") (pin "2") (pinfunction "2_2") (pintype "passive"))
      (node (ref "U$6") (pin "MTCK/12") (pinfunction "MTCK/12_MTCK/12") (pintype "bidirectional"))
    )
    (net (code "12") (name "Net-(R18-Pad2)") (class "Default")
      (node (ref "R18") (pin "2") (pinfunction "2_2") (pintype "passive"))
      (node (ref "U$6") (pin "SD_CLK/21") (pinfunction "SD_CLK/21_SD_CLK/21") (pintype "bidirectional"))
    )
    (net (code "13") (name "Net-(R25-Pad2)") (class "Default")
      (node (ref "R25") (pin "2") (pinfunction "2_2") (pintype "passive"))
      (node (ref "U$8") (pin "G") (pinfunction "G_G") (pintype "bidirectional"))
    )
    (net (code "14") (name "Net-(R26-Pad2)") (class "Default")
      (node (ref "R26") (pin "2") (pinfunction "2_2") (pintype "passive"))
      (node (ref "U$8") (pin "R") (pinfunction "R_R") (pintype "bidirectional"))
    )
    (net (code "15") (name "Net-(R27-Pad2)") (class "Default")
      (node (ref "R27") (pin "2") (pinfunction "2_2") (pintype "passive"))
      (node (ref "U$8") (pin "B") (pinfunction "B_B") (pintype "bidirectional"))
    )
    (net (code "16") (name "Net-(R28-Pad2)") (class "Default")
      (node (ref "R28") (pin "2") (pinfunction "2_2") (pintype "passive"))
      (node (ref "U$11") (pin "B") (pinfunction "B_B") (pintype "bidirectional"))
    )
    (net (code "17") (name "Net-(R29-Pad2)") (class "Default")
      (node (ref "R29") (pin "2") (pinfunction "2_2") (pintype "passive"))
      (node (ref "U$11") (pin "R") (pinfunction "R_R") (pintype "bidirectional"))
    )
    (net (code "18") (name "Net-(R30-Pad2)") (class "Default")
      (node (ref "R30") (pin "2") (pinfunction "2_2") (pintype "passive"))
      (node (ref "U$11") (pin "G") (pinfunction "G_G") (pintype "bidirectional"))
    )
    (net (code "19") (name "Net-(R31-Pad2)") (class "Default")
      (node (ref "R31") (pin "2") (pinfunction "2_2") (pintype "passive"))
      (node (ref "U$13") (pin "B") (pinfunction "B_B") (pintype "bidirectional"))
    )
    (net (code "20") (name "Net-(R32-Pad2)") (class "Default")
      (node (ref "R32") (pin "2") (pinfunction "2_2") (pintype "passive"))
      (node (ref "U$13") (pin "R") (pinfunction "R_R") (pintype "bidirectional"))
    )
    (net (code "21") (name "Net-(R33-Pad2)") (class "Default")
      (node (ref "R33") (pin "2") (pinfunction "2_2") (pintype "passive"))
      (node (ref "U$13") (pin "G") (pinfunction "G_G") (pintype "bidirectional"))
    )
    (net (code "22") (name "Net-(R34-Pad2)") (class "Default")
      (node (ref "R34") (pin "2") (pinfunction "2_2") (pintype "passive"))
      (node (ref "U$14") (pin "B") (pinfunction "B_B") (pintype "bidirectional"))
    )
    (net (code "23") (name "Net-(R35-Pad2)") (class "Default")
      (node (ref "R35") (pin "2") (pinfunction "2_2") (pintype "passive"))
      (node (ref "U$14") (pin "R") (pinfunction "R_R") (pintype "bidirectional"))
    )
    (net (code "24") (name "Net-(R36-Pad2)") (class "Default")
      (node (ref "R36") (pin "2") (pinfunction "2_2") (pintype "passive"))
      (node (ref "U$14") (pin "G") (pinfunction "G_G") (pintype "bidirectional"))
    )
    (net (code "25") (name "Net-(R37-Pad2)") (class "Default")
      (node (ref "R37") (pin "2") (pinfunction "2_2") (pintype "passive"))
      (node (ref "U$15") (pin "B") (pinfunction "B_B") (pintype "bidirectional"))
    )
    (net (code "26") (name "Net-(R38-Pad2)") (class "Default")
      (node (ref "R38") (pin "2") (pinfunction "2_2") (pintype "passive"))
      (node (ref "U$15") (pin "R") (pinfunction "R_R") (pintype "bidirectional"))
    )
    (net (code "27") (name "Net-(R39-Pad2)") (class "Default")
      (node (ref "R39") (pin "2") (pinfunction "2_2") (pintype "passive"))
      (node (ref "U$15") (pin "G") (pinfunction "G_G") (pintype "bidirectional"))
    )
    (net (code "28") (name "Net-(R40-Pad2)") (class "Default")
      (node (ref "R40") (pin "2") (pinfunction "2_2") (pintype "passive"))
      (node (ref "U$16") (pin "B") (pinfunction "B_B") (pintype "bidirectional"))
    )
    (net (code "29") (name "Net-(R41-Pad2)") (class "Default")
      (node (ref "R41") (pin "2") (pinfunction "2_2") (pintype "passive"))
      (node (ref "U$16") (pin "R") (pinfunction "R_R") (pintype "bidirectional"))
    )
    (net (code "30") (name "Net-(R42-Pad2)") (class "Default")
      (node (ref "R42") (pin "2") (pinfunction "2_2") (pintype "passive"))
      (node (ref "U$16") (pin "G") (pinfunction "G_G") (pintype "bidirectional"))
    )
    (net (code "31") (name "Net-(R43-Pad2)") (class "Default")
      (node (ref "R43") (pin "2") (pinfunction "2_2") (pintype "passive"))
      (node (ref "U$17") (pin "B") (pinfunction "B_B") (pintype "bidirectional"))
    )
    (net (code "32") (name "Net-(R44-Pad2)") (class "Default")
      (node (ref "R44") (pin "2") (pinfunction "2_2") (pintype "passive"))
      (node (ref "U$17") (pin "R") (pinfunction "R_R") (pintype "bidirectional"))
    )
    (net (code "33") (name "Net-(R45-Pad2)") (class "Default")
      (node (ref "R45") (pin "2") (pinfunction "2_2") (pintype "passive"))
      (node (ref "U$17") (pin "G") (pinfunction "G_G") (pintype "bidirectional"))
    )
    (net (code "34") (name "Net-(R46-Pad2)") (class "Default")
      (node (ref "R46") (pin "2") (pinfunction "2_2") (pintype "passive"))
      (node (ref "U$18") (pin "B") (pinfunction "B_B") (pintype "bidirectional"))
    )
    (net (code "35") (name "Net-(R47-Pad2)") (class "Default")
      (node (ref "R47") (pin "2") (pinfunction "2_2") (pintype "passive"))
      (node (ref "U$18") (pin "R") (pinfunction "R_R") (pintype "bidirectional"))
    )
    (net (code "36") (name "Net-(R48-Pad2)") (class "Default")
      (node (ref "R48") (pin "2") (pinfunction "2_2") (pintype "passive"))
      (node (ref "U$18") (pin "G") (pinfunction "G_G") (pintype "bidirectional"))
    )
    (net (code "37") (name "Net-(R51-Pad2)") (class "Default")
      (node (ref "R51") (pin "2") (pinfunction "2_2") (pintype "passive"))
      (node (ref "U$6") (pin "MTDO/13") (pinfunction "MTDO/13_MTDO/13") (pintype "bidirectional"))
    )
    (net (code "38") (name "Net-(S1-P)") (class "Default")
      (node (ref "JP5") (pin "2") (pinfunction "2_2") (pintype "passive"))
      (node (ref "S1") (pin "2") (pinfunction "P_2") (pintype "passive"))
    )
    (net (code "39") (name "Net-(U$1-SIGNAL)") (class "Default")
      (node (ref "C6") (pin "1") (pinfunction "1_1") (pintype "passive"))
      (node (ref "L7") (pin "1") (pinfunction "1_1") (pintype "passive"))
      (node (ref "U$1") (pin "FEED") (pinfunction "SIGNAL_FEED") (pintype "bidirectional"))
    )
    (net (code "40") (name "Net-(U$2-SIGNAL)") (class "Default")
      (node (ref "C12") (pin "1") (pinfunction "1_1") (pintype "passive"))
      (node (ref "C13") (pin "2") (pinfunction "2_2") (pintype "passive"))
      (node (ref "U$2") (pin "FEED") (pinfunction "SIGNAL_FEED") (pintype "bidirectional"))
    )
    (net (code "41") (name "Net-(U$3-CLK)") (class "Default")
      (node (ref "R18") (pin "1") (pinfunction "1_1") (pintype "passive"))
      (node (ref "U$3") (pin "6") (pinfunction "CLK_6") (pintype "bidirectional"))
    )
    (net (code "42") (name "Net-(U$3-CS#)") (class "Default")
      (node (ref "U$3") (pin "1") (pinfunction "CS#_1") (pintype "bidirectional"))
      (node (ref "U$6") (pin "SD_CMD/20") (pinfunction "SD_CMD/20_SD_CMD/20") (pintype "bidirectional"))
    )
    (net (code "43") (name "Net-(U$3-DIO)") (class "Default")
      (node (ref "U$3") (pin "5") (pinfunction "DIO_5") (pintype "bidirectional"))
      (node (ref "U$6") (pin "SD_DATA_1/23") (pinfunction "SD_DATA_1/23_SD_DATA_1/23") (pintype "bidirectional"))
    )
    (net (code "44") (name "Net-(U$3-DO)") (class "Default")
      (node (ref "U$3") (pin "2") (pinfunction "DO_2") (pintype "bidirectional"))
      (node (ref "U$6") (pin "SD_DATA_0/22") (pinfunction "SD_DATA_0/22_SD_DATA_0/22") (pintype "bidirectional"))
    )
    (net (code "45") (name "Net-(U$3-HOLD#)") (class "Default")
      (node (ref "U$3") (pin "7") (pinfunction "HOLD#_7") (pintype "bidirectional"))
      (node (ref "U$6") (pin "SD_DATA_2/18") (pinfunction "SD_DATA_2/18_SD_DATA_2/18") (pintype "bidirectional"))
    )
    (net (code "46") (name "Net-(U$3-WP#)") (class "Default")
      (node (ref "U$3") (pin "3") (pinfunction "WP#_3") (pintype "bidirectional"))
      (node (ref "U$6") (pin "SD_DATA_3/19") (pinfunction "SD_DATA_3/19_SD_DATA_3/19") (pintype "bidirectional"))
    )
    (net (code "47") (name "Net-(U$4-ANT1{slash}12)") (class "Default")
      (node (ref "L2") (pin "1") (pinfunction "1_1") (pintype "passive"))
      (node (ref "L5") (pin "2") (pinfunction "2_2") (pintype "passive"))
      (node (ref "U$4") (pin "12") (pinfunction "ANT1/12_12") (pintype "bidirectional"))
    )
    (net (code "48") (name "Net-(U$4-ANT2{slash}13)") (class "Default")
      (node (ref "L5") (pin "1") (pinfunction "1_1") (pintype "passive"))
      (node (ref "L6") (pin "1") (pinfunction "1_1") (pintype "passive"))
      (node (ref "U$4") (pin "13") (pinfunction "ANT2/13_13") (pintype "bidirectional"))
    )
    (net (code "49") (name "Net-(U$4-DVDD{slash}19)") (class "Default")
      (node (ref "C8") (pin "2") (pinfunction "2_2") (pintype "passive"))
      (node (ref "U$4") (pin "19") (pinfunction "DVDD/19_19") (pintype "bidirectional"))
    )
    (net (code "50") (name "Net-(U$4-IREF{slash}16)") (class "Default")
      (node (ref "R12") (pin "1") (pinfunction "1_1") (pintype "passive"))
      (node (ref "U$4") (pin "16") (pinfunction "IREF/16_16") (pintype "bidirectional"))
    )
    (net (code "51") (name "Net-(U$4-VDD_PA{slash}11)") (class "Default")
      (node (ref "C10") (pin "1") (pinfunction "1_1") (pintype "passive"))
      (node (ref "C9") (pin "1") (pinfunction "1_1") (pintype "passive"))
      (node (ref "L2") (pin "2") (pinfunction "2_2") (pintype "passive"))
      (node (ref "U$4") (pin "11") (pinfunction "VDD_PA/11_11") (pintype "bidirectional"))
    )
    (net (code "52") (name "Net-(U$4-XC1{slash}10)") (class "Default")
      (node (ref "C15") (pin "1") (pinfunction "1_1") (pintype "passive"))
      (node (ref "R11") (pin "2") (pinfunction "2_2") (pintype "passive"))
      (node (ref "U$4") (pin "10") (pinfunction "XC1/10_10") (pintype "bidirectional"))
      (node (ref "Y4") (pin "3") (pinfunction "2_3") (pintype "passive"))
    )
    (net (code "53") (name "Net-(U$4-XC2{slash}9)") (class "Default")
      (node (ref "C14") (pin "1") (pinfunction "1_1") (pintype "passive"))
      (node (ref "R11") (pin "1") (pinfunction "1_1") (pintype "passive"))
      (node (ref "U$4") (pin "9") (pinfunction "XC2/9_9") (pintype "bidirectional"))
      (node (ref "Y4") (pin "1") (pinfunction "1_1") (pintype "passive"))
    )
    (net (code "54") (name "Net-(U$7-NC{slash}TDI)") (class "Default")
      (node (ref "R52") (pin "2") (pinfunction "2_2") (pintype "passive"))
      (node (ref "U$7") (pin "8") (pinfunction "NC/TDI_8") (pintype "bidirectional"))
      (node (ref "U1") (pin "23") (pinfunction "PTA1_23") (pintype "bidirectional"))
    )
    (net (code "55") (name "Net-(U$7-SWO{slash}TDO)") (class "Default")
      (node (ref "U$7") (pin "6") (pinfunction "SWO/TDO_6") (pintype "bidirectional"))
      (node (ref "U1") (pin "24") (pinfunction "PTA2_24") (pintype "bidirectional"))
    )
    (net (code "56") (name "Net-(U$7-~{RESET})") (class "Default")
      (node (ref "R53") (pin "2") (pinfunction "2_2") (pintype "passive"))
      (node (ref "U$7") (pin "10") (pinfunction "~{RESET}_10") (pintype "bidirectional"))
      (node (ref "U1") (pin "34") (pinfunction "RESET_B_34") (pintype "bidirectional"))
    )
    (net (code "57") (name "Net-(U$20-A0)") (class "Default")
      (node (ref "R21") (pin "1") (pinfunction "1_1") (pintype "passive"))
      (node (ref "U$20") (pin "22") (pinfunction "A0_22") (pintype "bidirectional"))
    )
    (net (code "58") (name "Net-(U$20-A1)") (class "Default")
      (node (ref "R20") (pin "1") (pinfunction "1_1") (pintype "passive"))
      (node (ref "U$20") (pin "23") (pinfunction "A1_23") (pintype "bidirectional"))
    )
    (net (code "59") (name "Net-(U$20-A2)") (class "Default")
      (node (ref "R19") (pin "1") (pinfunction "1_1") (pintype "passive"))
      (node (ref "U$20") (pin "24") (pinfunction "A2_24") (pintype "bidirectional"))
    )
    (net (code "60") (name "Net-(U$20-LED0)") (class "Default")
      (node (ref "R26") (pin "1") (pinfunction "1_1") (pintype "passive"))
      (node (ref "U$20") (pin "1") (pinfunction "LED0_1") (pintype "bidirectional"))
    )
    (net (code "61") (name "Net-(U$20-LED1)") (class "Default")
      (node (ref "R25") (pin "1") (pinfunction "1_1") (pintype "passive"))
      (node (ref "U$20") (pin "2") (pinfunction "LED1_2") (pintype "bidirectional"))
    )
    (net (code "62") (name "Net-(U$20-LED2)") (class "Default")
      (node (ref "R27") (pin "1") (pinfunction "1_1") (pintype "passive"))
      (node (ref "U$20") (pin "3") (pinfunction "LED2_3") (pintype "bidirectional"))
    )
    (net (code "63") (name "Net-(U$20-LED3)") (class "Default")
      (node (ref "R29") (pin "1") (pinfunction "1_1") (pintype "passive"))
      (node (ref "U$20") (pin "4") (pinfunction "LED3_4") (pintype "bidirectional"))
    )
    (net (code "64") (name "Net-(U$20-LED4)") (class "Default")
      (node (ref "R30") (pin "1") (pinfunction "1_1") (pintype "passive"))
      (node (ref "U$20") (pin "5") (pinfunction "LED4_5") (pintype "bidirectional"))
    )
    (net (code "65") (name "Net-(U$20-LED5)") (class "Default")
      (node (ref "R28") (pin "1") (pinfunction "1_1") (pintype "passive"))
      (node (ref "U$20") (pin "6") (pinfunction "LED5_6") (pintype "bidirectional"))
    )
    (net (code "66") (name "Net-(U$20-LED6)") (class "Default")
      (node (ref "R32") (pin "1") (pinfunction "1_1") (pintype "passive"))
      (node (ref "U$20") (pin "7") (pinfunction "LED6_7") (pintype "bidirectional"))
    )
    (net (code "67") (name "Net-(U$20-LED7)") (class "Default")
      (node (ref "R33") (pin "1") (pinfunction "1_1") (pintype "passive"))
      (node (ref "U$20") (pin "8") (pinfunction "LED7_8") (pintype "bidirectional"))
    )
    (net (code "68") (name "Net-(U$20-LED8)") (class "Default")
      (node (ref "R31") (pin "1") (pinfunction "1_1") (pintype "passive"))
      (node (ref "U$20") (pin "10") (pinfunction "LED8_10") (pintype "bidirectional"))
    )
    (net (code "69") (name "Net-(U$20-LED9)") (class "Default")
      (node (ref "R35") (pin "1") (pinfunction "1_1") (pintype "passive"))
      (node (ref "U$20") (pin "11") (pinfunction "LED9_11") (pintype "bidirectional"))
    )
    (net (code "70") (name "Net-(U$20-LED10)") (class "Default")
      (node (ref "R36") (pin "1") (pinfunction "1_1") (pintype "passive"))
      (node (ref "U$20") (pin "12") (pinfunction "LED10_12") (pintype "bidirectional"))
    )
    (net (code "71") (name "Net-(U$20-LED11)") (class "Default")
      (node (ref "R34") (pin "1") (pinfunction "1_1") (pintype "passive"))
      (node (ref "U$20") (pin "13") (pinfunction "LED11_13") (pintype "bidirectional"))
    )
    (net (code "72") (name "Net-(U$21-A0)") (class "Default")
      (node (ref "R22") (pin "1") (pinfunction "1_1") (pintype "passive"))
      (node (ref "U$21") (pin "22") (pinfunction "A0_22") (pintype "bidirectional"))
    )
    (net (code "73") (name "Net-(U$21-A1)") (class "Default")
      (node (ref "R23") (pin "1") (pinfunction "1_1") (pintype "passive"))
      (node (ref "U$21") (pin "23") (pinfunction "A1_23") (pintype "bidirectional"))
    )
    (net (code "74") (name "Net-(U$21-A2)") (class "Default")
      (node (ref "R24") (pin "1") (pinfunction "1_1") (pintype "passive"))
      (node (ref "U$21") (pin "24") (pinfunction "A2_24") (pintype "bidirectional"))
    )
    (net (code "75") (name "Net-(U$21-LED0)") (class "Default")
      (node (ref "R38") (pin "1") (pinfunction "1_1") (pintype "passive"))
      (node (ref "U$21") (pin "1") (pinfunction "LED0_1") (pintype "bidirectional"))
    )
    (net (code "76") (name "Net-(U$21-LED1)") (class "Default")
      (node (ref "R39") (pin "1") (pinfunction "1_1") (pintype "passive"))
      (node (ref "U$21") (pin "2") (pinfunction "LED1_2") (pintype "bidirectional"))
    )
    (net (code "77") (name "Net-(U$21-LED2)") (class "Default")
      (node (ref "R37") (pin "1") (pinfunction "1_1") (pintype "passive"))
      (node (ref "U$21") (pin "3") (pinfunction "LED2_3") (pintype "bidirectional"))
    )
    (net (code "78") (name "Net-(U$21-LED3)") (class "Default")
      (node (ref "R41") (pin "1") (pinfunction "1_1") (pintype "passive"))
      (node (ref "U$21") (pin "4") (pinfunction "LED3_4") (pintype "bidirectional"))
    )
    (net (code "79") (name "Net-(U$21-LED4)") (class "Default")
      (node (ref "R42") (pin "1") (pinfunction "1_1") (pintype "passive"))
      (node (ref "U$21") (pin "5") (pinfunction "LED4_5") (pintype "bidirectional"))
    )
    (net (code "80") (name "Net-(U$21-LED5)") (class "Default")
      (node (ref "R40") (pin "1") (pinfunction "1_1") (pintype "passive"))
      (node (ref "U$21") (pin "6") (pinfunction "LED5_6") (pintype "bidirectional"))
    )
    (net (code "81") (name "Net-(U$21-LED6)") (class "Default")
      (node (ref "R44") (pin "1") (pinfunction "1_1") (pintype "passive"))
      (node (ref "U$21") (pin "7") (pinfunction "LED6_7") (pintype "bidirectional"))
    )
    (net (code "82") (name "Net-(U$21-LED7)") (class "Default")
      (node (ref "R45") (pin "1") (pinfunction "1_1") (pintype "passive"))
      (node (ref "U$21") (pin "8") (pinfunction "LED7_8") (pintype "bidirectional"))
    )
    (net (code "83") (name "Net-(U$21-LED8)") (class "Default")
      (node (ref "R43") (pin "1") (pinfunction "1_1") (pintype "passive"))
      (node (ref "U$21") (pin "10") (pinfunction "LED8_10") (pintype "bidirectional"))
    )
    (net (code "84") (name "Net-(U$21-LED9)") (class "Default")
      (node (ref "R47") (pin "1") (pinfunction "1_1") (pintype "passive"))
      (node (ref "U$21") (pin "11") (pinfunction "LED9_11") (pintype "bidirectional"))
    )
    (net (code "85") (name "Net-(U$21-LED10)") (class "Default")
      (node (ref "R48") (pin "1") (pinfunction "1_1") (pintype "passive"))
      (node (ref "U$21") (pin "12") (pinfunction "LED10_12") (pintype "bidirectional"))
    )
    (net (code "86") (name "Net-(U$21-LED11)") (class "Default")
      (node (ref "R46") (pin "1") (pinfunction "1_1") (pintype "passive"))
      (node (ref "U$21") (pin "13") (pinfunction "LED11_13") (pintype "bidirectional"))
    )
    (net (code "87") (name "Net-(U1-EXTAL32)") (class "Default")
      (node (ref "C32") (pin "2") (pinfunction "2_2") (pintype "passive"))
      (node (ref "U1") (pin "20") (pinfunction "EXTAL32_20") (pintype "bidirectional"))
      (node (ref "Y1") (pin "P$1") (pinfunction "1_P$1") (pintype "passive"))
    )
    (net (code "88") (name "Net-(U1-PTA18)") (class "Default")
      (node (ref "C29") (pin "2") (pinfunction "2_2") (pintype "passive"))
      (node (ref "U1") (pin "32") (pinfunction "PTA18_32") (pintype "bidirectional"))
      (node (ref "Y2") (pin "3") (pinfunction "2_3") (pintype "passive"))
    )
    (net (code "89") (name "Net-(U1-PTA19)") (class "Default")
      (node (ref "C30") (pin "2") (pinfunction "2_2") (pintype "passive"))
      (node (ref "U1") (pin "33") (pinfunction "PTA19_33") (pintype "bidirectional"))
      (node (ref "Y2") (pin "1") (pinfunction "1_1") (pintype "passive"))
    )
    (net (code "90") (name "Net-(U1-PTD6)") (class "Default")
      (node (ref "R8") (pin "1") (pinfunction "1_1") (pintype "passive"))
      (node (ref "U1") (pin "63") (pinfunction "PTD6_63") (pintype "bidirectional"))
    )
    (net (code "91") (name "Net-(U1-PTD7)") (class "Default")
      (node (ref "R17") (pin "1") (pinfunction "1_1") (pintype "passive"))
      (node (ref "U1") (pin "64") (pinfunction "PTD7_64") (pintype "bidirectional"))
    )
    (net (code "92") (name "Net-(U1-VDDA)") (class "Default")
      (node (ref "C17") (pin "1") (pinfunction "1_1") (pintype "passive"))
      (node (ref "L3") (pin "1") (pinfunction "1_1") (pintype "passive"))
      (node (ref "R16") (pin "1") (pinfunction "1_1") (pintype "passive"))
      (node (ref "U1") (pin "13") (pinfunction "VDDA_13") (pintype "bidirectional"))
    )
    (net (code "93") (name "Net-(U1-VREFH)") (class "Default")
      (node (ref "C11") (pin "1") (pinfunction "1_1") (pintype "passive"))
      (node (ref "R16") (pin "2") (pinfunction "2_2") (pintype "passive"))
      (node (ref "U1") (pin "14") (pinfunction "VREFH_14") (pintype "bidirectional"))
    )
    (net (code "94") (name "Net-(U1-VREFL)") (class "Default")
      (node (ref "C11") (pin "2") (pinfunction "2_2") (pintype "passive"))
      (node (ref "C16") (pin "2") (pinfunction "2_2") (pintype "passive"))
      (node (ref "C17") (pin "2") (pinfunction "2_2") (pintype "passive"))
      (node (ref "L4") (pin "2") (pinfunction "2_2") (pintype "passive"))
      (node (ref "U1") (pin "15") (pinfunction "VREFL_15") (pintype "bidirectional"))
      (node (ref "U1") (pin "16") (pinfunction "VSSA_16") (pintype "bidirectional"))
    )
    (net (code "95") (name "Net-(U1-VREF_OUT)") (class "Default")
      (node (ref "C16") (pin "1") (pinfunction "1_1") (pintype "passive"))
      (node (ref "U1") (pin "17") (pinfunction "VREF_OUT_17") (pintype "bidirectional"))
    )
    (net (code "96") (name "Net-(U1-XTAL32)") (class "Default")
      (node (ref "C31") (pin "2") (pinfunction "2_2") (pintype "passive"))
      (node (ref "U1") (pin "19") (pinfunction "XTAL32_19") (pintype "bidirectional"))
      (node (ref "Y1") (pin "P$2") (pinfunction "2_P$2") (pintype "passive"))
    )
    (net (code "97") (name "Net-(U2-FB)") (class "Default")
      (node (ref "R6") (pin "2") (pinfunction "2_2") (pintype "passive"))
      (node (ref "R7") (pin "1") (pinfunction "1_1") (pintype "passive"))
      (node (ref "U2") (pin "10") (pinfunction "FB_10") (pintype "passive"))
    )
    (net (code "98") (name "Net-(U2-L)") (class "Default")
      (node (ref "L1") (pin "1") (pinfunction "1_1") (pintype "passive"))
      (node (ref "U2") (pin "3") (pinfunction "L_3") (pintype "passive"))
    )
    (net (code "99") (name "Net-(U2-UVLO)") (class "Default")
      (node (ref "C2") (pin "2") (pinfunction "2_2") (pintype "passive"))
      (node (ref "R3") (pin "1") (pinfunction "1_1") (pintype "passive"))
      (node (ref "R4") (pin "2") (pinfunction "2_2") (pintype "passive"))
      (node (ref "U2") (pin "7") (pinfunction "UVLO_7") (pintype "passive"))
    )
    (net (code "100") (name "Net-(U2-VAUX)") (class "Default")
      (node (ref "C4") (pin "1") (pinfunction "1_1") (pintype "passive"))
      (node (ref "U2") (pin "1") (pinfunction "VAUX_1") (pintype "passive"))
    )
    (net (code "101") (name "Net-(U3-REGOUT)") (class "Default")
      (node (ref "C27") (pin "2") (pinfunction "2_2") (pintype "passive"))
      (node (ref "U3") (pin "10") (pinfunction "REGOUT_10") (pintype "bidirectional"))
    )
    (net (code "102") (name "Net-(Y3-2)") (class "Default")
      (node (ref "C23") (pin "1") (pinfunction "1_1") (pintype "passive"))
      (node (ref "U$6") (pin "XTAL_IN/28") (pinfunction "XTAL_IN/28_XTAL_IN/28") (pintype "bidirectional"))
      (node (ref "Y3") (pin "3") (pinfunction "2_3") (pintype "passive"))
    )
    (net (code "103") (name "PS") (class "Default")
      (node (ref "R2") (pin "2") (pinfunction "2_2") (pintype "passive"))
      (node (ref "U2") (pin "8") (pinfunction "PS_8") (pintype "input"))
    )
    (net (code "104") (name "PTA0") (class "Default")
      (node (ref "R50") (pin "2") (pinfunction "2_2") (pintype "passive"))
      (node (ref "U$7") (pin "4") (pinfunction "SWDCLK/TCK_4") (pintype "bidirectional"))
      (node (ref "U1") (pin "22") (pinfunction "PTA0_22") (pintype "bidirectional"))
    )
    (net (code "105") (name "PTA3") (class "Default")
      (node (ref "R49") (pin "2") (pinfunction "2_2") (pintype "passive"))
      (node (ref "U$7") (pin "2") (pinfunction "SWDIO/TMS_2") (pintype "bidirectional"))
      (node (ref "U1") (pin "25") (pinfunction "PTA3_25") (pintype "bidirectional"))
    )
    (net (code "106") (name "PTB0") (class "Default")
      (node (ref "U1") (pin "35") (pinfunction "PTB0_35") (pintype "bidirectional"))
      (node (ref "U3") (pin "12") (pinfunction "INT_12") (pintype "bidirectional"))
    )
    (net (code "107") (name "PTB1") (class "Default")
      (node (ref "U1") (pin "36") (pinfunction "PTB1_36") (pintype "bidirectional"))
      (node (ref "U3") (pin "11") (pinfunction "FSYNC_11") (pintype "bidirectional"))
    )
    (net (code "108") (name "PTB16") (class "Default")
      (node (ref "U$6") (pin "U0TXD/26") (pinfunction "U0TXD/26_U0TXD/26") (pintype "bidirectional"))
      (node (ref "U1") (pin "39") (pinfunction "PTB16_39") (pintype "bidirectional"))
    )
    (net (code "109") (name "PTB17") (class "Default")
      (node (ref "U$6") (pin "U0RXD/25") (pinfunction "U0RXD/25_U0RXD/25") (pintype "bidirectional"))
      (node (ref "U1") (pin "40") (pinfunction "PTB17_40") (pintype "bidirectional"))
    )
    (net (code "110") (name "PTB18") (class "Default")
      (node (ref "U$6") (pin "GPIO0/15") (pinfunction "GPIO0/15_GPIO0/15") (pintype "bidirectional"))
      (node (ref "U1") (pin "41") (pinfunction "PTB18_41") (pintype "bidirectional"))
    )
    (net (code "111") (name "PTB19") (class "Default")
      (node (ref "U$6") (pin "GPIO2/14") (pinfunction "GPIO2/14_GPIO2/14") (pintype "bidirectional"))
      (node (ref "U1") (pin "42") (pinfunction "PTB19_42") (pintype "bidirectional"))
    )
    (net (code "112") (name "PTC0") (class "Default")
      (node (ref "R15") (pin "1") (pinfunction "1_1") (pintype "passive"))
      (node (ref "U$6") (pin "EXT_RSTB/32") (pinfunction "EXT_RSTB/32_EXT_RSTB/32") (pintype "bidirectional"))
      (node (ref "U1") (pin "43") (pinfunction "PTC0_43") (pintype "bidirectional"))
    )
    (net (code "113") (name "PTC1") (class "Default")
      (node (ref "U$6") (pin "CHIP_EN/7") (pinfunction "CHIP_EN/7_CHIP_EN/7") (pintype "bidirectional"))
      (node (ref "U1") (pin "44") (pinfunction "PTC1_44") (pintype "bidirectional"))
    )
    (net (code "114") (name "PTC3") (class "Default")
      (node (ref "U$6") (pin "XPD_DCDC/8") (pinfunction "XPD_DCDC/8_XPD_DCDC/8") (pintype "bidirectional"))
      (node (ref "U1") (pin "46") (pinfunction "PTC3_46") (pintype "bidirectional"))
    )
    (net (code "115") (name "PTC4") (class "Default")
      (node (ref "U$4") (pin "2") (pinfunction "CSN/2_2") (pintype "bidirectional"))
      (node (ref "U1") (pin "49") (pinfunction "PTC4_49") (pintype "bidirectional"))
    )
    (net (code "116") (name "PTC5") (class "Default")
      (node (ref "U$4") (pin "3") (pinfunction "SCK/3_3") (pintype "bidirectional"))
      (node (ref "U1") (pin "50") (pinfunction "PTC5_50") (pintype "bidirectional"))
    )
    (net (code "117") (name "PTC6") (class "Default")
      (node (ref "U$4") (pin "4") (pinfunction "MOSI/4_4") (pintype "bidirectional"))
      (node (ref "U1") (pin "51") (pinfunction "PTC6_51") (pintype "bidirectional"))
    )
    (net (code "118") (name "PTC7") (class "Default")
      (node (ref "U$4") (pin "5") (pinfunction "MISO/5_5") (pintype "bidirectional"))
      (node (ref "U1") (pin "52") (pinfunction "PTC7_52") (pintype "bidirectional"))
    )
    (net (code "119") (name "PTC8") (class "Default")
      (node (ref "U$4") (pin "6") (pinfunction "IRQ/6_6") (pintype "bidirectional"))
      (node (ref "U1") (pin "53") (pinfunction "PTC8_53") (pintype "bidirectional"))
    )
    (net (code "120") (name "PTC9") (class "Default")
      (node (ref "U$4") (pin "1") (pinfunction "CE/1_1") (pintype "bidirectional"))
      (node (ref "U1") (pin "54") (pinfunction "PTC9_54") (pintype "bidirectional"))
    )
    (net (code "121") (name "PTC10") (class "Default")
      (node (ref "JP1") (pin "12") (pinfunction "12_12") (pintype "passive"))
      (node (ref "U1") (pin "55") (pinfunction "PTC10_55") (pintype "bidirectional"))
    )
    (net (code "122") (name "PTC11") (class "Default")
      (node (ref "JP1") (pin "11") (pinfunction "11_11") (pintype "passive"))
      (node (ref "U1") (pin "56") (pinfunction "PTC11_56") (pintype "bidirectional"))
    )
    (net (code "123") (name "PTD0") (class "Default")
      (node (ref "JP1") (pin "10") (pinfunction "10_10") (pintype "passive"))
      (node (ref "U1") (pin "57") (pinfunction "PTD0_57") (pintype "bidirectional"))
    )
    (net (code "124") (name "PTD1") (class "Default")
      (node (ref "JP1") (pin "9") (pinfunction "9_9") (pintype "passive"))
      (node (ref "U1") (pin "58") (pinfunction "PTD1_58") (pintype "bidirectional"))
    )
    (net (code "125") (name "PTD2") (class "Default")
      (node (ref "JP1") (pin "8") (pinfunction "8_8") (pintype "passive"))
      (node (ref "U1") (pin "59") (pinfunction "PTD2_59") (pintype "bidirectional"))
    )
    (net (code "126") (name "PTD3") (class "Default")
      (node (ref "JP1") (pin "7") (pinfunction "7_7") (pintype "passive"))
      (node (ref "U1") (pin "60") (pinfunction "PTD3_60") (pintype "bidirectional"))
    )
    (net (code "127") (name "PTD4") (class "Default")
      (node (ref "JP1") (pin "6") (pinfunction "6_6") (pintype "passive"))
      (node (ref "U1") (pin "61") (pinfunction "PTD4_61") (pintype "bidirectional"))
    )
    (net (code "128") (name "PTD5") (class "Default")
      (node (ref "JP1") (pin "5") (pinfunction "5_5") (pintype "passive"))
      (node (ref "U1") (pin "62") (pinfunction "PTD5_62") (pintype "bidirectional"))
    )
    (net (code "129") (name "SCL") (class "Default")
      (node (ref "R14") (pin "2") (pinfunction "2_2") (pintype "passive"))
      (node (ref "U$20") (pin "19") (pinfunction "SCL_19") (pintype "bidirectional"))
      (node (ref "U$21") (pin "19") (pinfunction "SCL_19") (pintype "bidirectional"))
      (node (ref "U1") (pin "37") (pinfunction "PTB2_37") (pintype "bidirectional"))
      (node (ref "U3") (pin "23") (pinfunction "SCLK_23") (pintype "bidirectional"))
    )
    (net (code "130") (name "SDA") (class "Default")
      (node (ref "R13") (pin "2") (pinfunction "2_2") (pintype "passive"))
      (node (ref "U$20") (pin "20") (pinfunction "SDA_20") (pintype "bidirectional"))
      (node (ref "U$21") (pin "20") (pinfunction "SDA_20") (pintype "bidirectional"))
      (node (ref "U1") (pin "38") (pinfunction "PTB3_38") (pintype "bidirectional"))
      (node (ref "U3") (pin "24") (pinfunction "SDA/MOSI_24") (pintype "bidirectional"))
    )
    (net (code "131") (name "SOFTPOWER") (class "Default")
      (node (ref "R10") (pin "1") (pinfunction "1_1") (pintype "passive"))
      (node (ref "U2") (pin "6") (pinfunction "EN_6") (pintype "input"))
    )
    (net (code "132") (name "USB_D_N") (class "Default")
      (node (ref "U1") (pin "6") (pinfunction "USB0_DM_6") (pintype "bidirectional"))
    )
    (net (code "133") (name "USB_D_P") (class "Default")
      (node (ref "U1") (pin "5") (pinfunction "USB0_DP_5") (pintype "bidirectional"))
    )
    (net (code "134") (name "VCC") (class "Default")
      (node (ref "C1") (pin "1") (pinfunction "1_1") (pintype "passive"))
      (node (ref "C2") (pin "1") (pinfunction "1_1") (pintype "passive"))
      (node (ref "L1") (pin "2") (pinfunction "2_2") (pintype "passive"))
      (node (ref "R10") (pin "2") (pinfunction "2_2") (pintype "passive"))
      (node (ref "R2") (pin "1") (pinfunction "1_1") (pintype "passive"))
      (node (ref "R3") (pin "2") (pinfunction "2_2") (pintype "passive"))
      (node (ref "S1") (pin "1") (pinfunction "O_1") (pintype "passive"))
      (node (ref "U2") (pin "5") (pinfunction "VIN_5") (pintype "power_in"))
    )
    (net (code "135") (name "unconnected-(S1-S-Pad3)") (class "Default")
      (node (ref "S1") (pin "3") (pinfunction "S_3") (pintype "passive"))
    )
    (net (code "136") (name "unconnected-(U$6-PadDVDD{slash}24)") (class "Default")
      (node (ref "U$6") (pin "DVDD/24") (pinfunction "DVDD/24_DVDD/24") (pintype "bidirectional"))
    )
    (net (code "137") (name "unconnected-(U$6-PadMTDI{slash}10)") (class "Default")
      (node (ref "U$6") (pin "MTDI/10") (pinfunction "MTDI/10_MTDI/10") (pintype "bidirectional"))
    )
    (net (code "138") (name "unconnected-(U$6-PadMTMS{slash}9)") (class "Default")
      (node (ref "U$6") (pin "MTMS/9") (pinfunction "MTMS/9_MTMS/9") (pintype "bidirectional"))
    )
    (net (code "139") (name "unconnected-(U$6-PadTOUT{slash}6)") (class "Default")
      (node (ref "U$6") (pin "TOUT/6") (pinfunction "TOUT/6_TOUT/6") (pintype "bidirectional"))
    )
    (net (code "140") (name "unconnected-(U$6-PadVDD_RTC{slash}5)") (class "Default")
      (node (ref "U$6") (pin "VDD_RTC/5") (pinfunction "VDD_RTC/5_VDD_RTC/5") (pintype "bidirectional"))
    )
    (net (code "141") (name "unconnected-(U$6-PadVDD{slash}16)") (class "Default")
      (node (ref "U$6") (pin "VDD/16") (pinfunction "VDD/16_VDD/16") (pintype "bidirectional"))
    )
    (net (code "142") (name "unconnected-(U$20-LED12-Pad14)") (class "Default")
      (node (ref "U$20") (pin "14") (pinfunction "LED12_14") (pintype "bidirectional"))
    )
    (net (code "143") (name "unconnected-(U$20-LED13-Pad15)") (class "Default")
      (node (ref "U$20") (pin "15") (pinfunction "LED13_15") (pintype "bidirectional"))
    )
    (net (code "144") (name "unconnected-(U$20-LED14-Pad16)") (class "Default")
      (node (ref "U$20") (pin "16") (pinfunction "LED14_16") (pintype "bidirectional"))
    )
    (net (code "145") (name "unconnected-(U$20-LED15-Pad17)") (class "Default")
      (node (ref "U$20") (pin "17") (pinfunction "LED15_17") (pintype "bidirectional"))
    )
    (net (code "146") (name "unconnected-(U$20-LED16-Pad18)") (class "Default")
      (node (ref "U$20") (pin "18") (pinfunction "LED16_18") (pintype "bidirectional"))
    )
    (net (code "147") (name "unconnected-(U$21-LED12-Pad14)") (class "Default")
      (node (ref "U$21") (pin "14") (pinfunction "LED12_14") (pintype "bidirectional"))
    )
    (net (code "148") (name "unconnected-(U$21-LED13-Pad15)") (class "Default")
      (node (ref "U$21") (pin "15") (pinfunction "LED13_15") (pintype "bidirectional"))
    )
    (net (code "149") (name "unconnected-(U$21-LED14-Pad16)") (class "Default")
      (node (ref "U$21") (pin "16") (pinfunction "LED14_16") (pintype "bidirectional"))
    )
    (net (code "150") (name "unconnected-(U$21-LED15-Pad17)") (class "Default")
      (node (ref "U$21") (pin "17") (pinfunction "LED15_17") (pintype "bidirectional"))
    )
    (net (code "151") (name "unconnected-(U$21-LED16-Pad18)") (class "Default")
      (node (ref "U$21") (pin "18") (pinfunction "LED16_18") (pintype "bidirectional"))
    )
    (net (code "152") (name "unconnected-(U1-ADC0_DM0-Pad10)") (class "Default")
      (node (ref "U1") (pin "10") (pinfunction "ADC0_DM0_10") (pintype "bidirectional"))
    )
    (net (code "153") (name "unconnected-(U1-ADC0_DM3-Pad12)") (class "Default")
      (node (ref "U1") (pin "12") (pinfunction "ADC0_DM3_12") (pintype "bidirectional"))
    )
    (net (code "154") (name "unconnected-(U1-ADC0_DP0-Pad9)") (class "Default")
      (node (ref "U1") (pin "9") (pinfunction "ADC0_DP0_9") (pintype "bidirectional"))
    )
    (net (code "155") (name "unconnected-(U1-ADC0_DP3-Pad11)") (class "Default")
      (node (ref "U1") (pin "11") (pinfunction "ADC0_DP3_11") (pintype "bidirectional"))
    )
    (net (code "156") (name "unconnected-(U1-DAC0-Pad18)") (class "Default")
      (node (ref "U1") (pin "18") (pinfunction "DAC0_18") (pintype "bidirectional"))
    )
    (net (code "157") (name "unconnected-(U1-PTA4-Pad26)") (class "Default")
      (node (ref "U1") (pin "26") (pinfunction "PTA4_26") (pintype "bidirectional"))
    )
    (net (code "158") (name "unconnected-(U1-PTA5-Pad27)") (class "Default")
      (node (ref "U1") (pin "27") (pinfunction "PTA5_27") (pintype "bidirectional"))
    )
    (net (code "159") (name "unconnected-(U1-PTA12-Pad28)") (class "Default")
      (node (ref "U1") (pin "28") (pinfunction "PTA12_28") (pintype "bidirectional"))
    )
    (net (code "160") (name "unconnected-(U1-PTA13-Pad29)") (class "Default")
      (node (ref "U1") (pin "29") (pinfunction "PTA13_29") (pintype "bidirectional"))
    )
    (net (code "161") (name "unconnected-(U1-PTE0-Pad1)") (class "Default")
      (node (ref "U1") (pin "1") (pinfunction "PTE0_1") (pintype "bidirectional"))
    )
    (net (code "162") (name "unconnected-(U1-PTE1-Pad2)") (class "Default")
      (node (ref "U1") (pin "2") (pinfunction "PTE1_2") (pintype "bidirectional"))
    )
    (net (code "163") (name "unconnected-(U3-AUX_CL-Pad7)") (class "Default")
      (node (ref "U3") (pin "7") (pinfunction "AUX_CL_7") (pintype "bidirectional"))
    )
    (net (code "164") (name "unconnected-(U3-AUX_DA-Pad21)") (class "Default")
      (node (ref "U3") (pin "21") (pinfunction "AUX_DA_21") (pintype "bidirectional"))
    )
  )
)
